# full_bridge_converter.net
KiCad netlist of a schematic drawn in Altium Designer
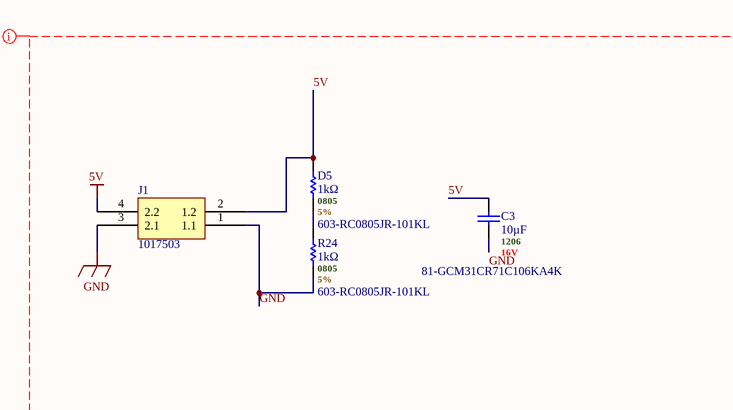
[diagram p0: full_bridge_converter.SchDoc, top left]
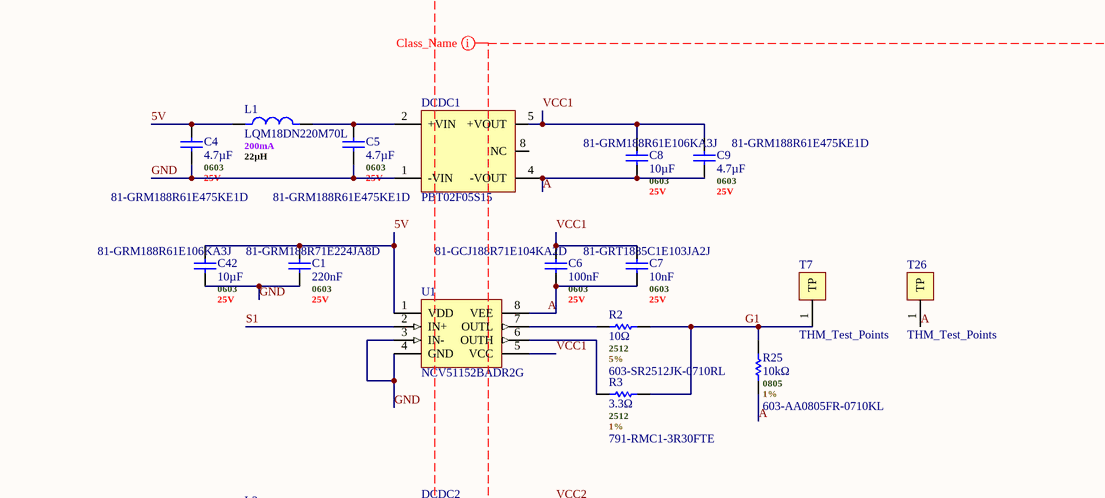
[diagram p1: full_bridge_converter.SchDoc, top right]
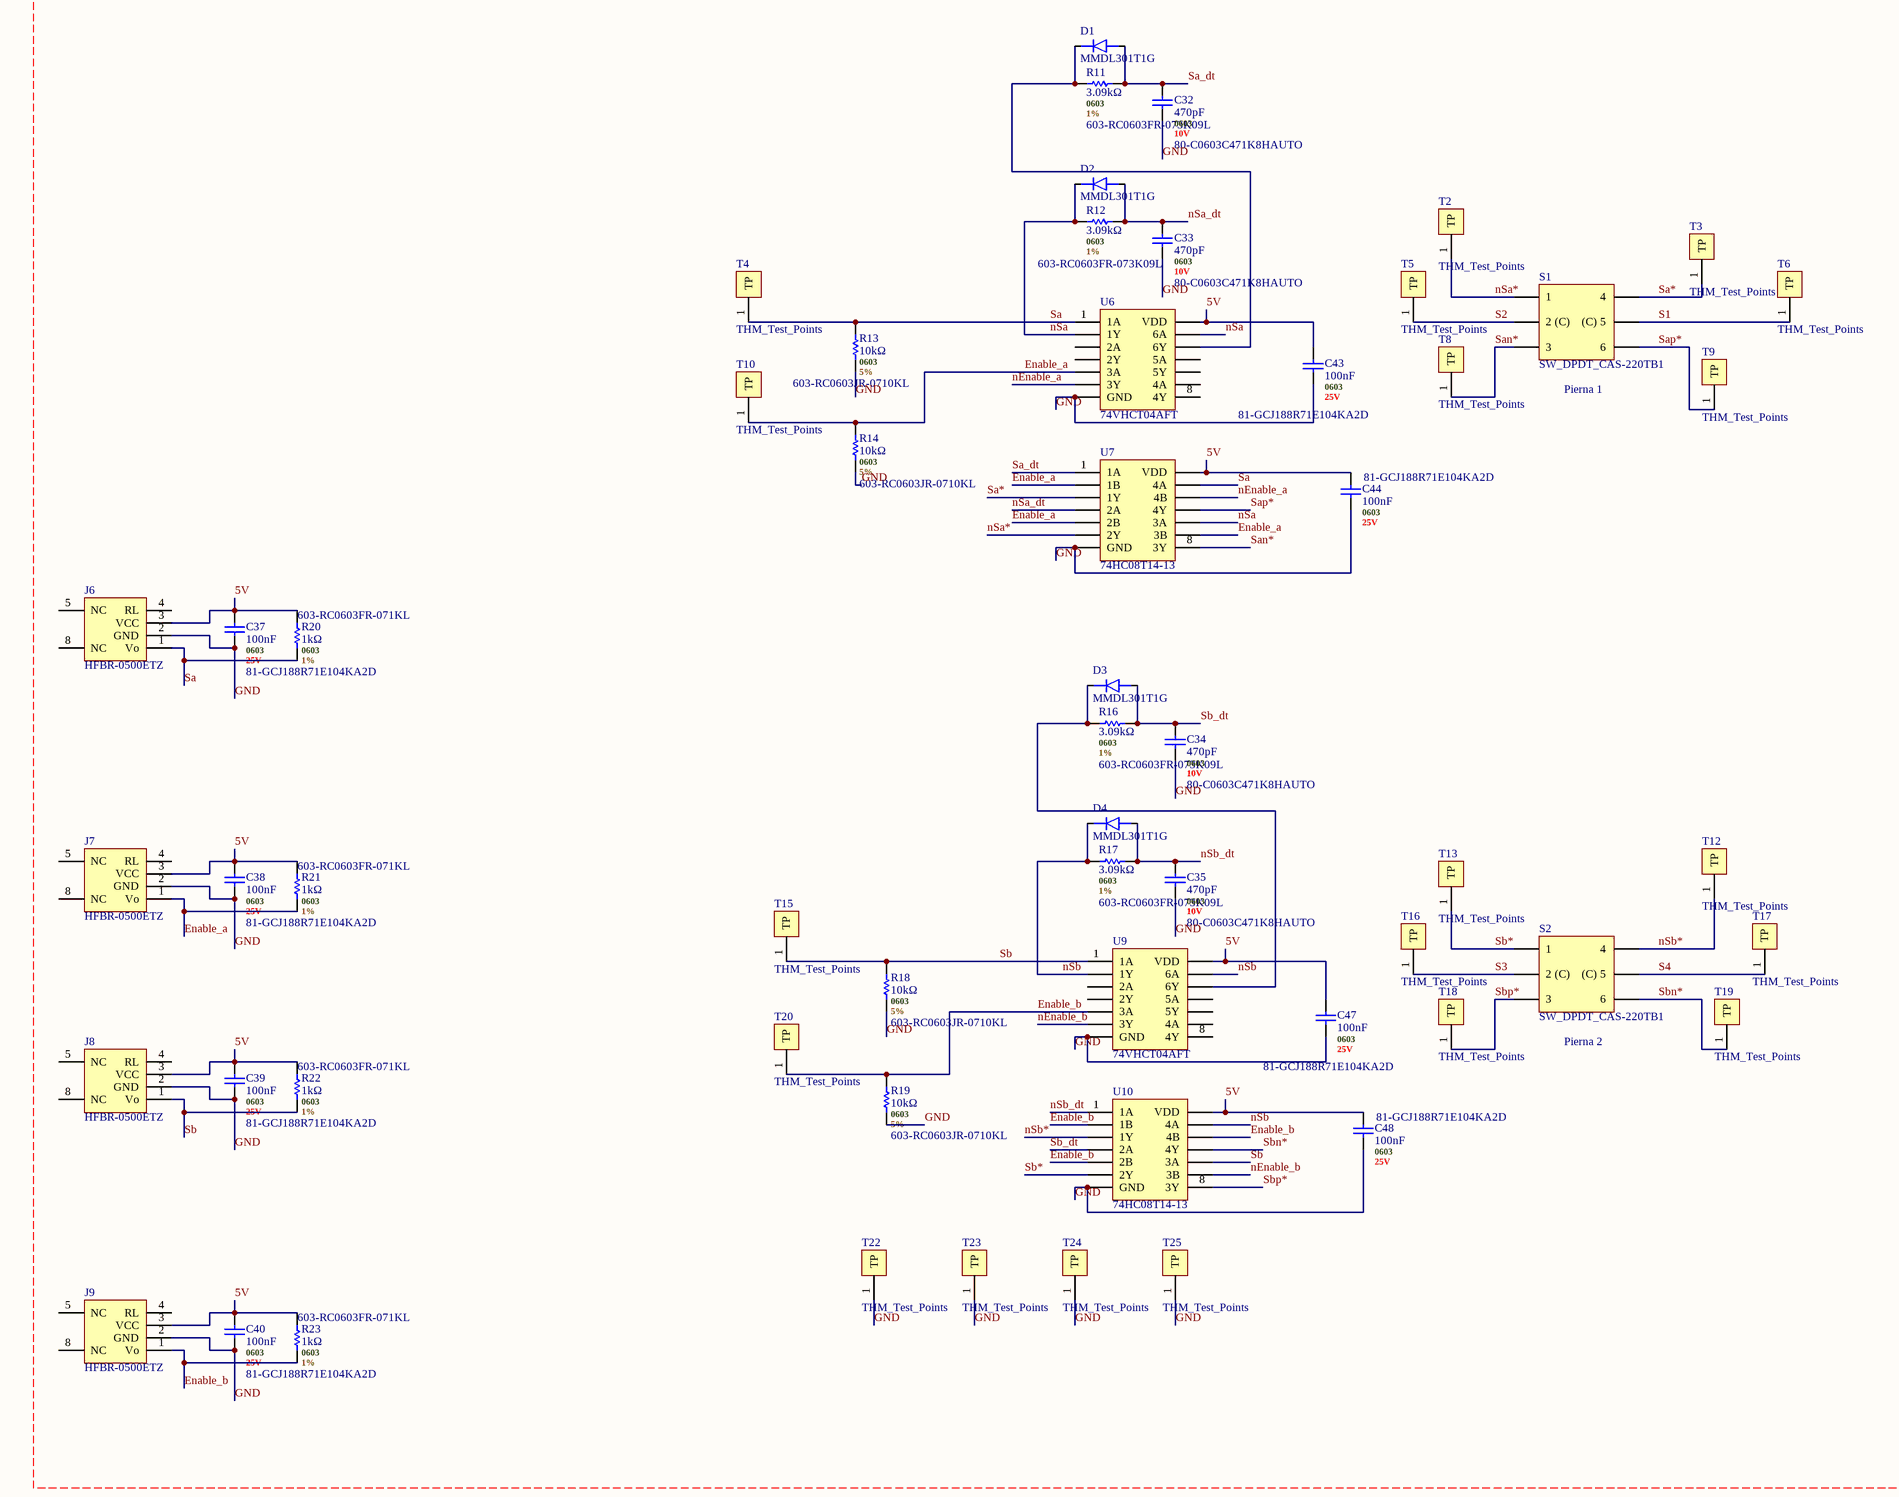
[diagram p2: full_bridge_converter.SchDoc, bottom left]
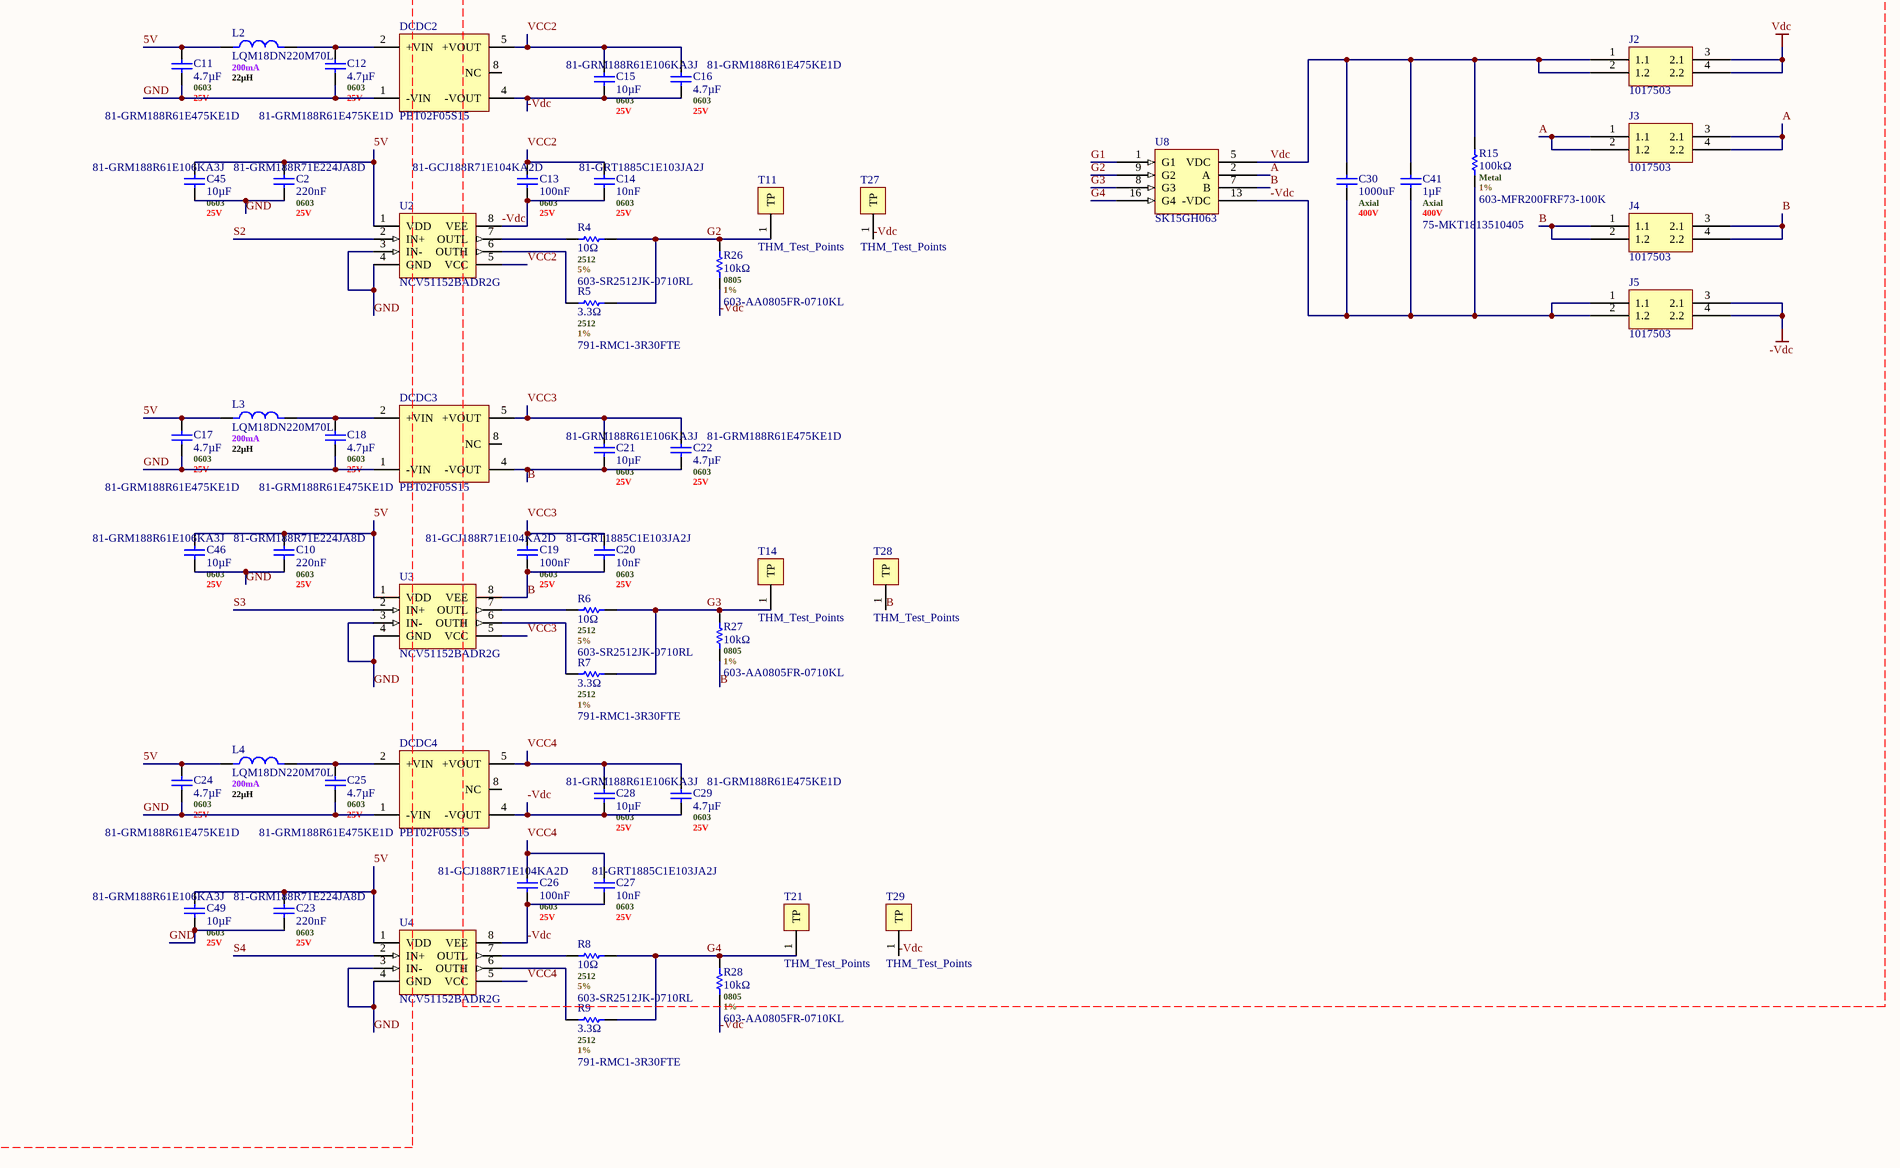
[diagram p3: full_bridge_converter.SchDoc, bottom right]

(export (version "E")
  (design (tool "Eeschema 10.0.6"))
  (components
    (comp (ref "C1")
      (value "220nF")
      (footprint "GRM188R71E224JA88D")
      (description "Ceramic Capacitor, Ceramic, 25V, 5% +Tol, 5% -Tol, X7R, 15% TC, 0.22uF, Surface Mount, 0603")
      (fields
        (field (name "MANUFACTURER") "Murata")
        (field (name "MANUFACTURER PART NUMBER") "GRM188R71E224JA88D")
        (field (name ".CASE/PACKAGE") "0603")
        (field (name ".VOLTAGE RATING (DC)") "25V")
        (field (name "SUPPLIER PART NUMBER 1") "81-GRM188R71E224JA8D")
      )
      (libsource (lib "CAP_GRM188R71E224JA88D") (part "CAP_GRM188R71E224JA88D"))
    )
    (comp (ref "C2")
      (value "220nF")
      (footprint "GRM188R71E224JA88D")
      (description "Ceramic Capacitor, Ceramic, 25V, 5% +Tol, 5% -Tol, X7R, 15% TC, 0.22uF, Surface Mount, 0603")
      (fields
        (field (name "MANUFACTURER") "Murata")
        (field (name "MANUFACTURER PART NUMBER") "GRM188R71E224JA88D")
        (field (name ".CASE/PACKAGE") "0603")
        (field (name ".VOLTAGE RATING (DC)") "25V")
        (field (name "SUPPLIER PART NUMBER 1") "81-GRM188R71E224JA8D")
      )
      (libsource (lib "CAP_GRM188R71E224JA88D") (part "CAP_GRM188R71E224JA88D"))
    )
    (comp (ref "C3")
      (value "10µF")
      (footprint "GCM31CR71C106KA64K")
      (description "16V 10uF X7R ±10% 1206 Multilayer Ceramic Capacitors MLCC - SMD/SMT ROHS")
      (fields
        (field (name "MANUFACTURER") "Murata")
        (field (name "MANUFACTURER PART NUMBER") "GCM31CR71C106KA64K")
        (field (name ".CASE/PACKAGE") "1206")
        (field (name ".VOLTAGE RATING (DC)") "16V")
        (field (name "SUPPLIER PART NUMBER 1") "81-GCM31CR71C106KA4K")
      )
      (libsource (lib "CAP_Murata_GCM31CR71C106KA64K") (part "GCM31CR71C106KA4K"))
    )
    (comp (ref "C4")
      (value "4.7µF")
      (footprint "GRM188R71E224JA88D")
      (description "0603 4.7 uF 25 V ±10 % Tolerance X5R SMT Multilayer Ceramic Capacitor")
      (fields
        (field (name "MANUFACTURER") "Murata")
        (field (name "MANUFACTURER PART NUMBER") "GRM188R61E475KE11D")
        (field (name ".CASE/PACKAGE") "0603")
        (field (name ".VOLTAGE RATING (DC)") "25V")
        (field (name "SUPPLIER PART NUMBER 1") "81-GRM188R61E475KE1D")
      )
      (libsource (lib "CAP_GRM188R61E475KE11D") (part "CAP_GRM188R61E475KE11D"))
    )
    (comp (ref "C5")
      (value "4.7µF")
      (footprint "GRM188R71E224JA88D")
      (description "0603 4.7 uF 25 V ±10 % Tolerance X5R SMT Multilayer Ceramic Capacitor")
      (fields
        (field (name "MANUFACTURER") "Murata")
        (field (name "MANUFACTURER PART NUMBER") "GRM188R61E475KE11D")
        (field (name ".CASE/PACKAGE") "0603")
        (field (name ".VOLTAGE RATING (DC)") "25V")
        (field (name "SUPPLIER PART NUMBER 1") "81-GRM188R61E475KE1D")
      )
      (libsource (lib "CAP_GRM188R61E475KE11D") (part "CAP_GRM188R61E475KE11D"))
    )
    (comp (ref "C6")
      (value "100nF")
      (footprint "GRM188R71E224JA88D")
      (description "Ceramic Capacitor, Ceramic, 25V, 10% +Tol, 10% -Tol, X7R, 15% TC, 0.1uF, Surface Mount, 0603")
      (fields
        (field (name "MANUFACTURER") "Murata")
        (field (name "MANUFACTURER PART NUMBER") "GCJ188R71E104KA12D")
        (field (name ".CASE/PACKAGE") "0603")
        (field (name ".VOLTAGE RATING (DC)") "25V")
        (field (name "SUPPLIER PART NUMBER 1") "81-GCJ188R71E104KA2D")
      )
      (libsource (lib "CAP_GCJ188R71E104KA12D") (part "CAP_GCJ188R71E104KA12D"))
    )
    (comp (ref "C7")
      (value "10nF")
      (footprint "GRM188R71E224JA88D")
      (description "Multi-Layer Ceramic Capacitor 0.01uF 25VDC C0G 5% 0603 Paper T/R")
      (fields
        (field (name "MANUFACTURER") "Murata")
        (field (name "MANUFACTURER PART NUMBER") "GRT1885C1E103JA02J")
        (field (name ".CASE/PACKAGE") "0603")
        (field (name ".VOLTAGE RATING (DC)") "25V")
        (field (name "SUPPLIER PART NUMBER 1") "81-GRT1885C1E103JA2J")
      )
      (libsource (lib "CAP_GRT1885C1E103JA02J") (part "GRT1885C1E103JA02J"))
    )
    (comp (ref "C8")
      (value "10µF")
      (footprint "GRM188R71E224JA88D")
      (description "Multilayer Ceramic Capacitor, 10 uF, 25 V, 10%, X5R, 0603 1608 Metric - T/R")
      (fields
        (field (name "MANUFACTURER") "Murata")
        (field (name "MANUFACTURER PART NUMBER") "GRM188R61E106KA73J")
        (field (name ".CASE/PACKAGE") "0603")
        (field (name ".VOLTAGE RATING (DC)") "25V")
        (field (name "SUPPLIER PART NUMBER 1") "81-GRM188R61E106KA3J")
      )
      (libsource (lib "CAP_GRM188R61E106KA73J") (part "CAP_GRM188R61E106KA73J"))
    )
    (comp (ref "C9")
      (value "4.7µF")
      (footprint "GRM188R71E224JA88D")
      (description "0603 4.7 uF 25 V ±10 % Tolerance X5R SMT Multilayer Ceramic Capacitor")
      (fields
        (field (name "MANUFACTURER") "Murata")
        (field (name "MANUFACTURER PART NUMBER") "GRM188R61E475KE11D")
        (field (name ".CASE/PACKAGE") "0603")
        (field (name ".VOLTAGE RATING (DC)") "25V")
        (field (name "SUPPLIER PART NUMBER 1") "81-GRM188R61E475KE1D")
      )
      (libsource (lib "CAP_GRM188R61E475KE11D") (part "CAP_GRM188R61E475KE11D"))
    )
    (comp (ref "C10")
      (value "220nF")
      (footprint "GRM188R71E224JA88D")
      (description "Ceramic Capacitor, Ceramic, 25V, 5% +Tol, 5% -Tol, X7R, 15% TC, 0.22uF, Surface Mount, 0603")
      (fields
        (field (name "MANUFACTURER") "Murata")
        (field (name "MANUFACTURER PART NUMBER") "GRM188R71E224JA88D")
        (field (name ".CASE/PACKAGE") "0603")
        (field (name ".VOLTAGE RATING (DC)") "25V")
        (field (name "SUPPLIER PART NUMBER 1") "81-GRM188R71E224JA8D")
      )
      (libsource (lib "CAP_GRM188R71E224JA88D") (part "CAP_GRM188R71E224JA88D"))
    )
    (comp (ref "C11")
      (value "4.7µF")
      (footprint "GRM188R71E224JA88D")
      (description "0603 4.7 uF 25 V ±10 % Tolerance X5R SMT Multilayer Ceramic Capacitor")
      (fields
        (field (name "MANUFACTURER") "Murata")
        (field (name "MANUFACTURER PART NUMBER") "GRM188R61E475KE11D")
        (field (name ".CASE/PACKAGE") "0603")
        (field (name ".VOLTAGE RATING (DC)") "25V")
        (field (name "SUPPLIER PART NUMBER 1") "81-GRM188R61E475KE1D")
      )
      (libsource (lib "CAP_GRM188R61E475KE11D") (part "CAP_GRM188R61E475KE11D"))
    )
    (comp (ref "C12")
      (value "4.7µF")
      (footprint "GRM188R71E224JA88D")
      (description "0603 4.7 uF 25 V ±10 % Tolerance X5R SMT Multilayer Ceramic Capacitor")
      (fields
        (field (name "MANUFACTURER") "Murata")
        (field (name "MANUFACTURER PART NUMBER") "GRM188R61E475KE11D")
        (field (name ".CASE/PACKAGE") "0603")
        (field (name ".VOLTAGE RATING (DC)") "25V")
        (field (name "SUPPLIER PART NUMBER 1") "81-GRM188R61E475KE1D")
      )
      (libsource (lib "CAP_GRM188R61E475KE11D") (part "CAP_GRM188R61E475KE11D"))
    )
    (comp (ref "C13")
      (value "100nF")
      (footprint "GRM188R71E224JA88D")
      (description "Ceramic Capacitor, Ceramic, 25V, 10% +Tol, 10% -Tol, X7R, 15% TC, 0.1uF, Surface Mount, 0603")
      (fields
        (field (name "MANUFACTURER") "Murata")
        (field (name "MANUFACTURER PART NUMBER") "GCJ188R71E104KA12D")
        (field (name ".CASE/PACKAGE") "0603")
        (field (name ".VOLTAGE RATING (DC)") "25V")
        (field (name "SUPPLIER PART NUMBER 1") "81-GCJ188R71E104KA2D")
      )
      (libsource (lib "CAP_GCJ188R71E104KA12D") (part "CAP_GCJ188R71E104KA12D"))
    )
    (comp (ref "C14")
      (value "10nF")
      (footprint "GRM188R71E224JA88D")
      (description "Multi-Layer Ceramic Capacitor 0.01uF 25VDC C0G 5% 0603 Paper T/R")
      (fields
        (field (name "MANUFACTURER") "Murata")
        (field (name "MANUFACTURER PART NUMBER") "GRT1885C1E103JA02J")
        (field (name ".CASE/PACKAGE") "0603")
        (field (name ".VOLTAGE RATING (DC)") "25V")
        (field (name "SUPPLIER PART NUMBER 1") "81-GRT1885C1E103JA2J")
      )
      (libsource (lib "CAP_GRT1885C1E103JA02J") (part "GRT1885C1E103JA02J"))
    )
    (comp (ref "C15")
      (value "10µF")
      (footprint "GRM188R71E224JA88D")
      (description "Multilayer Ceramic Capacitor, 10 uF, 25 V, 10%, X5R, 0603 1608 Metric - T/R")
      (fields
        (field (name "MANUFACTURER") "Murata")
        (field (name "MANUFACTURER PART NUMBER") "GRM188R61E106KA73J")
        (field (name ".CASE/PACKAGE") "0603")
        (field (name ".VOLTAGE RATING (DC)") "25V")
        (field (name "SUPPLIER PART NUMBER 1") "81-GRM188R61E106KA3J")
      )
      (libsource (lib "CAP_GRM188R61E106KA73J") (part "CAP_GRM188R61E106KA73J"))
    )
    (comp (ref "C16")
      (value "4.7µF")
      (footprint "GRM188R71E224JA88D")
      (description "0603 4.7 uF 25 V ±10 % Tolerance X5R SMT Multilayer Ceramic Capacitor")
      (fields
        (field (name "MANUFACTURER") "Murata")
        (field (name "MANUFACTURER PART NUMBER") "GRM188R61E475KE11D")
        (field (name ".CASE/PACKAGE") "0603")
        (field (name ".VOLTAGE RATING (DC)") "25V")
        (field (name "SUPPLIER PART NUMBER 1") "81-GRM188R61E475KE1D")
      )
      (libsource (lib "CAP_GRM188R61E475KE11D") (part "CAP_GRM188R61E475KE11D"))
    )
    (comp (ref "C17")
      (value "4.7µF")
      (footprint "GRM188R71E224JA88D")
      (description "0603 4.7 uF 25 V ±10 % Tolerance X5R SMT Multilayer Ceramic Capacitor")
      (fields
        (field (name "MANUFACTURER") "Murata")
        (field (name "MANUFACTURER PART NUMBER") "GRM188R61E475KE11D")
        (field (name ".CASE/PACKAGE") "0603")
        (field (name ".VOLTAGE RATING (DC)") "25V")
        (field (name "SUPPLIER PART NUMBER 1") "81-GRM188R61E475KE1D")
      )
      (libsource (lib "CAP_GRM188R61E475KE11D") (part "CAP_GRM188R61E475KE11D"))
    )
    (comp (ref "C18")
      (value "4.7µF")
      (footprint "GRM188R71E224JA88D")
      (description "0603 4.7 uF 25 V ±10 % Tolerance X5R SMT Multilayer Ceramic Capacitor")
      (fields
        (field (name "MANUFACTURER") "Murata")
        (field (name "MANUFACTURER PART NUMBER") "GRM188R61E475KE11D")
        (field (name ".CASE/PACKAGE") "0603")
        (field (name ".VOLTAGE RATING (DC)") "25V")
        (field (name "SUPPLIER PART NUMBER 1") "81-GRM188R61E475KE1D")
      )
      (libsource (lib "CAP_GRM188R61E475KE11D") (part "CAP_GRM188R61E475KE11D"))
    )
    (comp (ref "C19")
      (value "100nF")
      (footprint "GRM188R71E224JA88D")
      (description "Ceramic Capacitor, Ceramic, 25V, 10% +Tol, 10% -Tol, X7R, 15% TC, 0.1uF, Surface Mount, 0603")
      (fields
        (field (name "MANUFACTURER") "Murata")
        (field (name "MANUFACTURER PART NUMBER") "GCJ188R71E104KA12D")
        (field (name ".CASE/PACKAGE") "0603")
        (field (name ".VOLTAGE RATING (DC)") "25V")
        (field (name "SUPPLIER PART NUMBER 1") "81-GCJ188R71E104KA2D")
      )
      (libsource (lib "CAP_GCJ188R71E104KA12D") (part "CAP_GCJ188R71E104KA12D"))
    )
    (comp (ref "C20")
      (value "10nF")
      (footprint "GRM188R71E224JA88D")
      (description "Multi-Layer Ceramic Capacitor 0.01uF 25VDC C0G 5% 0603 Paper T/R")
      (fields
        (field (name "MANUFACTURER") "Murata")
        (field (name "MANUFACTURER PART NUMBER") "GRT1885C1E103JA02J")
        (field (name ".CASE/PACKAGE") "0603")
        (field (name ".VOLTAGE RATING (DC)") "25V")
        (field (name "SUPPLIER PART NUMBER 1") "81-GRT1885C1E103JA2J")
      )
      (libsource (lib "CAP_GRT1885C1E103JA02J") (part "GRT1885C1E103JA02J"))
    )
    (comp (ref "C21")
      (value "10µF")
      (footprint "GRM188R71E224JA88D")
      (description "Multilayer Ceramic Capacitor, 10 uF, 25 V, 10%, X5R, 0603 1608 Metric - T/R")
      (fields
        (field (name "MANUFACTURER") "Murata")
        (field (name "MANUFACTURER PART NUMBER") "GRM188R61E106KA73J")
        (field (name ".CASE/PACKAGE") "0603")
        (field (name ".VOLTAGE RATING (DC)") "25V")
        (field (name "SUPPLIER PART NUMBER 1") "81-GRM188R61E106KA3J")
      )
      (libsource (lib "CAP_GRM188R61E106KA73J") (part "CAP_GRM188R61E106KA73J"))
    )
    (comp (ref "C22")
      (value "4.7µF")
      (footprint "GRM188R71E224JA88D")
      (description "0603 4.7 uF 25 V ±10 % Tolerance X5R SMT Multilayer Ceramic Capacitor")
      (fields
        (field (name "MANUFACTURER") "Murata")
        (field (name "MANUFACTURER PART NUMBER") "GRM188R61E475KE11D")
        (field (name ".CASE/PACKAGE") "0603")
        (field (name ".VOLTAGE RATING (DC)") "25V")
        (field (name "SUPPLIER PART NUMBER 1") "81-GRM188R61E475KE1D")
      )
      (libsource (lib "CAP_GRM188R61E475KE11D") (part "CAP_GRM188R61E475KE11D"))
    )
    (comp (ref "C23")
      (value "220nF")
      (footprint "GRM188R71E224JA88D")
      (description "Ceramic Capacitor, Ceramic, 25V, 5% +Tol, 5% -Tol, X7R, 15% TC, 0.22uF, Surface Mount, 0603")
      (fields
        (field (name "MANUFACTURER") "Murata")
        (field (name "MANUFACTURER PART NUMBER") "GRM188R71E224JA88D")
        (field (name ".CASE/PACKAGE") "0603")
        (field (name ".VOLTAGE RATING (DC)") "25V")
        (field (name "SUPPLIER PART NUMBER 1") "81-GRM188R71E224JA8D")
      )
      (libsource (lib "CAP_GRM188R71E224JA88D") (part "CAP_GRM188R71E224JA88D"))
    )
    (comp (ref "C24")
      (value "4.7µF")
      (footprint "GRM188R71E224JA88D")
      (description "0603 4.7 uF 25 V ±10 % Tolerance X5R SMT Multilayer Ceramic Capacitor")
      (fields
        (field (name "MANUFACTURER") "Murata")
        (field (name "MANUFACTURER PART NUMBER") "GRM188R61E475KE11D")
        (field (name ".CASE/PACKAGE") "0603")
        (field (name ".VOLTAGE RATING (DC)") "25V")
        (field (name "SUPPLIER PART NUMBER 1") "81-GRM188R61E475KE1D")
      )
      (libsource (lib "CAP_GRM188R61E475KE11D") (part "CAP_GRM188R61E475KE11D"))
    )
    (comp (ref "C25")
      (value "4.7µF")
      (footprint "GRM188R71E224JA88D")
      (description "0603 4.7 uF 25 V ±10 % Tolerance X5R SMT Multilayer Ceramic Capacitor")
      (fields
        (field (name "MANUFACTURER") "Murata")
        (field (name "MANUFACTURER PART NUMBER") "GRM188R61E475KE11D")
        (field (name ".CASE/PACKAGE") "0603")
        (field (name ".VOLTAGE RATING (DC)") "25V")
        (field (name "SUPPLIER PART NUMBER 1") "81-GRM188R61E475KE1D")
      )
      (libsource (lib "CAP_GRM188R61E475KE11D") (part "CAP_GRM188R61E475KE11D"))
    )
    (comp (ref "C26")
      (value "100nF")
      (footprint "GRM188R71E224JA88D")
      (description "Ceramic Capacitor, Ceramic, 25V, 10% +Tol, 10% -Tol, X7R, 15% TC, 0.1uF, Surface Mount, 0603")
      (fields
        (field (name "MANUFACTURER") "Murata")
        (field (name "MANUFACTURER PART NUMBER") "GCJ188R71E104KA12D")
        (field (name ".CASE/PACKAGE") "0603")
        (field (name ".VOLTAGE RATING (DC)") "25V")
        (field (name "SUPPLIER PART NUMBER 1") "81-GCJ188R71E104KA2D")
      )
      (libsource (lib "CAP_GCJ188R71E104KA12D") (part "CAP_GCJ188R71E104KA12D"))
    )
    (comp (ref "C27")
      (value "10nF")
      (footprint "GRM188R71E224JA88D")
      (description "Multi-Layer Ceramic Capacitor 0.01uF 25VDC C0G 5% 0603 Paper T/R")
      (fields
        (field (name "MANUFACTURER") "Murata")
        (field (name "MANUFACTURER PART NUMBER") "GRT1885C1E103JA02J")
        (field (name ".CASE/PACKAGE") "0603")
        (field (name ".VOLTAGE RATING (DC)") "25V")
        (field (name "SUPPLIER PART NUMBER 1") "81-GRT1885C1E103JA2J")
      )
      (libsource (lib "CAP_GRT1885C1E103JA02J") (part "GRT1885C1E103JA02J"))
    )
    (comp (ref "C28")
      (value "10µF")
      (footprint "GRM188R71E224JA88D")
      (description "Multilayer Ceramic Capacitor, 10 uF, 25 V, 10%, X5R, 0603 1608 Metric - T/R")
      (fields
        (field (name "MANUFACTURER") "Murata")
        (field (name "MANUFACTURER PART NUMBER") "GRM188R61E106KA73J")
        (field (name ".CASE/PACKAGE") "0603")
        (field (name ".VOLTAGE RATING (DC)") "25V")
        (field (name "SUPPLIER PART NUMBER 1") "81-GRM188R61E106KA3J")
      )
      (libsource (lib "CAP_GRM188R61E106KA73J") (part "CAP_GRM188R61E106KA73J"))
    )
    (comp (ref "C29")
      (value "4.7µF")
      (footprint "GRM188R71E224JA88D")
      (description "0603 4.7 uF 25 V ±10 % Tolerance X5R SMT Multilayer Ceramic Capacitor")
      (fields
        (field (name "MANUFACTURER") "Murata")
        (field (name "MANUFACTURER PART NUMBER") "GRM188R61E475KE11D")
        (field (name ".CASE/PACKAGE") "0603")
        (field (name ".VOLTAGE RATING (DC)") "25V")
        (field (name "SUPPLIER PART NUMBER 1") "81-GRM188R61E475KE1D")
      )
      (libsource (lib "CAP_GRM188R61E475KE11D") (part "CAP_GRM188R61E475KE11D"))
    )
    (comp (ref "C30")
      (value "1000uF")
      (footprint "Pcb_Components:1316N")
      (fields
        (field (name "VOLTAGE") "400V")
        (field (name ".CASE/PACKAGE") "Axial")
        (field (name ".VOLTAGE RATING (DC)") "400V")
      )
      (libsource (lib "Sch_components") (part "Pana_400_1000"))
    )
    (comp (ref "C32")
      (value "470pF")
      (footprint "C0603 - MURATA")
      (description "Cap, 470Pf, 10V, Mlcc, 0603 Rohs Compliant: Yes ¦Kemet C0603C471K8HACAUTO")
      (fields
        (field (name "MANUFACTURER") "KEMET")
        (field (name "MANUFACTURER PART NUMBER") "C0603C471K8HACAUTO")
        (field (name ".CASE/PACKAGE") "0603")
        (field (name ".VOLTAGE RATING (DC)") "10V")
        (field (name "SUPPLIER PART NUMBER 1") "80-C0603C471K8HAUTO")
      )
      (libsource (lib "CAP_C0603C471K8HACAUTO") (part "CAP_Kemet_C0603C471K8HACAUTO"))
    )
    (comp (ref "C33")
      (value "470pF")
      (footprint "C0603 - MURATA")
      (description "Cap, 470Pf, 10V, Mlcc, 0603 Rohs Compliant: Yes ¦Kemet C0603C471K8HACAUTO")
      (fields
        (field (name "MANUFACTURER") "KEMET")
        (field (name "MANUFACTURER PART NUMBER") "C0603C471K8HACAUTO")
        (field (name ".CASE/PACKAGE") "0603")
        (field (name ".VOLTAGE RATING (DC)") "10V")
        (field (name "SUPPLIER PART NUMBER 1") "80-C0603C471K8HAUTO")
      )
      (libsource (lib "CAP_C0603C471K8HACAUTO") (part "CAP_Kemet_C0603C471K8HACAUTO"))
    )
    (comp (ref "C34")
      (value "470pF")
      (footprint "C0603 - MURATA")
      (description "Cap, 470Pf, 10V, Mlcc, 0603 Rohs Compliant: Yes ¦Kemet C0603C471K8HACAUTO")
      (fields
        (field (name "MANUFACTURER") "KEMET")
        (field (name "MANUFACTURER PART NUMBER") "C0603C471K8HACAUTO")
        (field (name ".CASE/PACKAGE") "0603")
        (field (name ".VOLTAGE RATING (DC)") "10V")
        (field (name "SUPPLIER PART NUMBER 1") "80-C0603C471K8HAUTO")
      )
      (libsource (lib "CAP_C0603C471K8HACAUTO") (part "CAP_Kemet_C0603C471K8HACAUTO"))
    )
    (comp (ref "C35")
      (value "470pF")
      (footprint "C0603 - MURATA")
      (description "Cap, 470Pf, 10V, Mlcc, 0603 Rohs Compliant: Yes ¦Kemet C0603C471K8HACAUTO")
      (fields
        (field (name "MANUFACTURER") "KEMET")
        (field (name "MANUFACTURER PART NUMBER") "C0603C471K8HACAUTO")
        (field (name ".CASE/PACKAGE") "0603")
        (field (name ".VOLTAGE RATING (DC)") "10V")
        (field (name "SUPPLIER PART NUMBER 1") "80-C0603C471K8HAUTO")
      )
      (libsource (lib "CAP_C0603C471K8HACAUTO") (part "CAP_Kemet_C0603C471K8HACAUTO"))
    )
    (comp (ref "C37")
      (value "100nF")
      (footprint "GRM188R71E224JA88D")
      (description "Ceramic Capacitor, Ceramic, 25V, 10% +Tol, 10% -Tol, X7R, 15% TC, 0.1uF, Surface Mount, 0603")
      (fields
        (field (name "MANUFACTURER") "Murata")
        (field (name "MANUFACTURER PART NUMBER") "GCJ188R71E104KA12D")
        (field (name ".CASE/PACKAGE") "0603")
        (field (name ".VOLTAGE RATING (DC)") "25V")
        (field (name "SUPPLIER PART NUMBER 1") "81-GCJ188R71E104KA2D")
      )
      (libsource (lib "CAP_GCJ188R71E104KA12D") (part "CAP_GCJ188R71E104KA12D"))
    )
    (comp (ref "C38")
      (value "100nF")
      (footprint "GRM188R71E224JA88D")
      (description "Ceramic Capacitor, Ceramic, 25V, 10% +Tol, 10% -Tol, X7R, 15% TC, 0.1uF, Surface Mount, 0603")
      (fields
        (field (name "MANUFACTURER") "Murata")
        (field (name "MANUFACTURER PART NUMBER") "GCJ188R71E104KA12D")
        (field (name ".CASE/PACKAGE") "0603")
        (field (name ".VOLTAGE RATING (DC)") "25V")
        (field (name "SUPPLIER PART NUMBER 1") "81-GCJ188R71E104KA2D")
      )
      (libsource (lib "CAP_GCJ188R71E104KA12D") (part "CAP_GCJ188R71E104KA12D"))
    )
    (comp (ref "C39")
      (value "100nF")
      (footprint "GRM188R71E224JA88D")
      (description "Ceramic Capacitor, Ceramic, 25V, 10% +Tol, 10% -Tol, X7R, 15% TC, 0.1uF, Surface Mount, 0603")
      (fields
        (field (name "MANUFACTURER") "Murata")
        (field (name "MANUFACTURER PART NUMBER") "GCJ188R71E104KA12D")
        (field (name ".CASE/PACKAGE") "0603")
        (field (name ".VOLTAGE RATING (DC)") "25V")
        (field (name "SUPPLIER PART NUMBER 1") "81-GCJ188R71E104KA2D")
      )
      (libsource (lib "CAP_GCJ188R71E104KA12D") (part "CAP_GCJ188R71E104KA12D"))
    )
    (comp (ref "C40")
      (value "100nF")
      (footprint "GRM188R71E224JA88D")
      (description "Ceramic Capacitor, Ceramic, 25V, 10% +Tol, 10% -Tol, X7R, 15% TC, 0.1uF, Surface Mount, 0603")
      (fields
        (field (name "MANUFACTURER") "Murata")
        (field (name "MANUFACTURER PART NUMBER") "GCJ188R71E104KA12D")
        (field (name ".CASE/PACKAGE") "0603")
        (field (name ".VOLTAGE RATING (DC)") "25V")
        (field (name "SUPPLIER PART NUMBER 1") "81-GCJ188R71E104KA2D")
      )
      (libsource (lib "CAP_GCJ188R71E104KA12D") (part "CAP_GCJ188R71E104KA12D"))
    )
    (comp (ref "C41")
      (value "1µF")
      (footprint "MKT1813510405")
      (description "Film Capacitor, Polyester, 400V, 10% +Tol, 10% -Tol, 1uF, Through Hole Mount")
      (fields
        (field (name "MANUFACTURER") "Vishay")
        (field (name "MANUFACTURER PART NUMBER") "MKT1813510405")
        (field (name ".CASE/PACKAGE") "Axial")
        (field (name ".VOLTAGE RATING (DC)") "400V")
        (field (name "SUPPLIER PART NUMBER 1") "75-MKT1813510405")
      )
      (libsource (lib "CAP_Vishay_MKT1813510405") (part "MKT1813510405"))
    )
    (comp (ref "C42")
      (value "10µF")
      (footprint "GRM188R71E224JA88D")
      (description "Multilayer Ceramic Capacitor, 10 uF, 25 V, 10%, X5R, 0603 1608 Metric - T/R")
      (fields
        (field (name "MANUFACTURER") "Murata")
        (field (name "MANUFACTURER PART NUMBER") "GRM188R61E106KA73J")
        (field (name ".CASE/PACKAGE") "0603")
        (field (name ".VOLTAGE RATING (DC)") "25V")
        (field (name "SUPPLIER PART NUMBER 1") "81-GRM188R61E106KA3J")
      )
      (libsource (lib "CAP_GRM188R61E106KA73J") (part "CAP_GRM188R61E106KA73J"))
    )
    (comp (ref "C43")
      (value "100nF")
      (footprint "GRM188R71E224JA88D")
      (description "Ceramic Capacitor, Ceramic, 25V, 10% +Tol, 10% -Tol, X7R, 15% TC, 0.1uF, Surface Mount, 0603")
      (fields
        (field (name "MANUFACTURER") "Murata")
        (field (name "MANUFACTURER PART NUMBER") "GCJ188R71E104KA12D")
        (field (name ".CASE/PACKAGE") "0603")
        (field (name ".VOLTAGE RATING (DC)") "25V")
        (field (name "SUPPLIER PART NUMBER 1") "81-GCJ188R71E104KA2D")
      )
      (libsource (lib "CAP_GCJ188R71E104KA12D") (part "CAP_GCJ188R71E104KA12D"))
    )
    (comp (ref "C44")
      (value "100nF")
      (footprint "GRM188R71E224JA88D")
      (description "Ceramic Capacitor, Ceramic, 25V, 10% +Tol, 10% -Tol, X7R, 15% TC, 0.1uF, Surface Mount, 0603")
      (fields
        (field (name "MANUFACTURER") "Murata")
        (field (name "MANUFACTURER PART NUMBER") "GCJ188R71E104KA12D")
        (field (name ".CASE/PACKAGE") "0603")
        (field (name ".VOLTAGE RATING (DC)") "25V")
        (field (name "SUPPLIER PART NUMBER 1") "81-GCJ188R71E104KA2D")
      )
      (libsource (lib "CAP_GCJ188R71E104KA12D") (part "CAP_GCJ188R71E104KA12D"))
    )
    (comp (ref "C45")
      (value "10µF")
      (footprint "GRM188R71E224JA88D")
      (description "Multilayer Ceramic Capacitor, 10 uF, 25 V, 10%, X5R, 0603 1608 Metric - T/R")
      (fields
        (field (name "MANUFACTURER") "Murata")
        (field (name "MANUFACTURER PART NUMBER") "GRM188R61E106KA73J")
        (field (name ".CASE/PACKAGE") "0603")
        (field (name ".VOLTAGE RATING (DC)") "25V")
        (field (name "SUPPLIER PART NUMBER 1") "81-GRM188R61E106KA3J")
      )
      (libsource (lib "CAP_GRM188R61E106KA73J") (part "CAP_GRM188R61E106KA73J"))
    )
    (comp (ref "C46")
      (value "10µF")
      (footprint "GRM188R71E224JA88D")
      (description "Multilayer Ceramic Capacitor, 10 uF, 25 V, 10%, X5R, 0603 1608 Metric - T/R")
      (fields
        (field (name "MANUFACTURER") "Murata")
        (field (name "MANUFACTURER PART NUMBER") "GRM188R61E106KA73J")
        (field (name ".CASE/PACKAGE") "0603")
        (field (name ".VOLTAGE RATING (DC)") "25V")
        (field (name "SUPPLIER PART NUMBER 1") "81-GRM188R61E106KA3J")
      )
      (libsource (lib "CAP_GRM188R61E106KA73J") (part "CAP_GRM188R61E106KA73J"))
    )
    (comp (ref "C47")
      (value "100nF")
      (footprint "GRM188R71E224JA88D")
      (description "Ceramic Capacitor, Ceramic, 25V, 10% +Tol, 10% -Tol, X7R, 15% TC, 0.1uF, Surface Mount, 0603")
      (fields
        (field (name "MANUFACTURER") "Murata")
        (field (name "MANUFACTURER PART NUMBER") "GCJ188R71E104KA12D")
        (field (name ".CASE/PACKAGE") "0603")
        (field (name ".VOLTAGE RATING (DC)") "25V")
        (field (name "SUPPLIER PART NUMBER 1") "81-GCJ188R71E104KA2D")
      )
      (libsource (lib "CAP_GCJ188R71E104KA12D") (part "CAP_GCJ188R71E104KA12D"))
    )
    (comp (ref "C48")
      (value "100nF")
      (footprint "GRM188R71E224JA88D")
      (description "Ceramic Capacitor, Ceramic, 25V, 10% +Tol, 10% -Tol, X7R, 15% TC, 0.1uF, Surface Mount, 0603")
      (fields
        (field (name "MANUFACTURER") "Murata")
        (field (name "MANUFACTURER PART NUMBER") "GCJ188R71E104KA12D")
        (field (name ".CASE/PACKAGE") "0603")
        (field (name ".VOLTAGE RATING (DC)") "25V")
        (field (name "SUPPLIER PART NUMBER 1") "81-GCJ188R71E104KA2D")
      )
      (libsource (lib "CAP_GCJ188R71E104KA12D") (part "CAP_GCJ188R71E104KA12D"))
    )
    (comp (ref "C49")
      (value "10µF")
      (footprint "GRM188R71E224JA88D")
      (description "Multilayer Ceramic Capacitor, 10 uF, 25 V, 10%, X5R, 0603 1608 Metric - T/R")
      (fields
        (field (name "MANUFACTURER") "Murata")
        (field (name "MANUFACTURER PART NUMBER") "GRM188R61E106KA73J")
        (field (name ".CASE/PACKAGE") "0603")
        (field (name ".VOLTAGE RATING (DC)") "25V")
        (field (name "SUPPLIER PART NUMBER 1") "81-GRM188R61E106KA3J")
      )
      (libsource (lib "CAP_GRM188R61E106KA73J") (part "CAP_GRM188R61E106KA73J"))
    )
    (comp (ref "D1")
      (value "MMDL301T1G")
      (footprint "DIOM2713X12N")
      (libsource (lib "Sch_components") (part "MMDL301T1G"))
    )
    (comp (ref "D2")
      (value "MMDL301T1G")
      (footprint "DIOM2713X12N")
      (libsource (lib "Sch_components") (part "MMDL301T1G"))
    )
    (comp (ref "D3")
      (value "MMDL301T1G")
      (footprint "DIOM2713X12N")
      (libsource (lib "Sch_components") (part "MMDL301T1G"))
    )
    (comp (ref "D4")
      (value "MMDL301T1G")
      (footprint "DIOM2713X12N")
      (libsource (lib "Sch_components") (part "MMDL301T1G"))
    )
    (comp (ref "D5")
      (value "1kΩ")
      (footprint "RC0805JR-101KL")
      (description "Res Thick Film 0805 1K Ohm 5% 0.125W(1/8W) ±100ppm/C Pad SMD T/R")
      (fields
        (field (name "MANUFACTURER") "Yageo Group")
        (field (name "MANUFACTURER PART NUMBER") "RC0805JR-101KL")
        (field (name ".CASE/PACKAGE") "0805")
        (field (name ".TOLERANCE") "5%")
        (field (name "SUPPLIER PART NUMBER 1") "603-RC0805JR-101KL")
      )
      (libsource (lib "RESISTOR_Yageo_RC0805JR-101KL") (part "RC0805JR-101KL"))
    )
    (comp (ref "DCDC1")
      (value "PBT02F05S15")
      (footprint "PBT02F05S15")
      (libsource (lib "Sch_components") (part "PBT02F05S15"))
    )
    (comp (ref "DCDC2")
      (value "PBT02F05S15")
      (footprint "PBT02F05S15")
      (libsource (lib "Sch_components") (part "PBT02F05S15"))
    )
    (comp (ref "DCDC3")
      (value "PBT02F05S15")
      (footprint "PBT02F05S15")
      (libsource (lib "Sch_components") (part "PBT02F05S15"))
    )
    (comp (ref "DCDC4")
      (value "PBT02F05S15")
      (footprint "PBT02F05S15")
      (libsource (lib "Sch_components") (part "PBT02F05S15"))
    )
    (comp (ref "J1") (value "1017503") (footprint "CONN_1017491") (libsource (lib "") (part "1017503_1")))
    (comp (ref "J2")
      (value "1017503")
      (footprint "CONN_1017491")
      (libsource (lib "Phoenix_1017503") (part "1017503"))
    )
    (comp (ref "J3")
      (value "1017503")
      (footprint "CONN_1017491")
      (libsource (lib "Phoenix_1017503") (part "1017503"))
    )
    (comp (ref "J4")
      (value "1017503")
      (footprint "CONN_1017491")
      (libsource (lib "Phoenix_1017503") (part "1017503"))
    )
    (comp (ref "J5")
      (value "1017503")
      (footprint "CONN_1017491")
      (libsource (lib "Phoenix_1017503") (part "1017503"))
    )
    (comp (ref "J6")
      (value "HFBR-0500ETZ")
      (footprint "HFBR-0500ETZ")
      (description "Receptor Connector Optical Fiber")
      (libsource (lib "FibraOpt_Broadcom_HFBR") (part "HFBR-0500ETZ"))
    )
    (comp (ref "J7")
      (value "HFBR-0500ETZ")
      (footprint "HFBR-0500ETZ")
      (description "Receptor Connector Optical Fiber")
      (libsource (lib "FibraOpt_Broadcom_HFBR") (part "HFBR-0500ETZ"))
    )
    (comp (ref "J8")
      (value "HFBR-0500ETZ")
      (footprint "HFBR-0500ETZ")
      (description "Receptor Connector Optical Fiber")
      (libsource (lib "FibraOpt_Broadcom_HFBR") (part "HFBR-0500ETZ"))
    )
    (comp (ref "J9")
      (value "HFBR-0500ETZ")
      (footprint "HFBR-0500ETZ")
      (description "Receptor Connector Optical Fiber")
      (libsource (lib "FibraOpt_Broadcom_HFBR") (part "HFBR-0500ETZ"))
    )
    (comp (ref "L1")
      (value "LQM18DN220M70L")
      (footprint "LQM18DN220M70L")
      (description "Inductor Power Shielded Multi-Layer 22uH 20% 1MHz Ferrite 0.2A 3.12Ohm DCR 0603 T/R")
      (fields
        (field (name "MANUFACTURER") "Murata")
        (field (name "TOLERANCE") "20%")
        (field (name ".RMS CURRENT (IRMS)") "200mA")
        (field (name ".VALUE") "22µH")
      )
      (libsource (lib "INDUC_Murata_LQM18DN220M70L") (part "LQM18DN220M70L"))
    )
    (comp (ref "L2")
      (value "LQM18DN220M70L")
      (footprint "LQM18DN220M70L")
      (description "Inductor Power Shielded Multi-Layer 22uH 20% 1MHz Ferrite 0.2A 3.12Ohm DCR 0603 T/R")
      (fields
        (field (name "MANUFACTURER") "Murata")
        (field (name "TOLERANCE") "20%")
        (field (name ".RMS CURRENT (IRMS)") "200mA")
        (field (name ".VALUE") "22µH")
      )
      (libsource (lib "INDUC_Murata_LQM18DN220M70L") (part "LQM18DN220M70L"))
    )
    (comp (ref "L3")
      (value "LQM18DN220M70L")
      (footprint "LQM18DN220M70L")
      (description "Inductor Power Shielded Multi-Layer 22uH 20% 1MHz Ferrite 0.2A 3.12Ohm DCR 0603 T/R")
      (fields
        (field (name "MANUFACTURER") "Murata")
        (field (name "TOLERANCE") "20%")
        (field (name ".RMS CURRENT (IRMS)") "200mA")
        (field (name ".VALUE") "22µH")
      )
      (libsource (lib "INDUC_Murata_LQM18DN220M70L") (part "LQM18DN220M70L"))
    )
    (comp (ref "L4")
      (value "LQM18DN220M70L")
      (footprint "LQM18DN220M70L")
      (description "Inductor Power Shielded Multi-Layer 22uH 20% 1MHz Ferrite 0.2A 3.12Ohm DCR 0603 T/R")
      (fields
        (field (name "MANUFACTURER") "Murata")
        (field (name "TOLERANCE") "20%")
        (field (name ".RMS CURRENT (IRMS)") "200mA")
        (field (name ".VALUE") "22µH")
      )
      (libsource (lib "INDUC_Murata_LQM18DN220M70L") (part "LQM18DN220M70L"))
    )
    (comp (ref "R2")
      (value "10Ω")
      (footprint "SR2512JK-0710RL")
      (fields
        (field (name "MANUFACTURER") "Yageo Group")
        (field (name "MANUFACTURER PART NUMBER") "SR2512JK-0710RL")
        (field (name "TOLERANCE") "5%")
        (field (name ".CASE/PACKAGE") "2512")
        (field (name ".TOLERANCE") "5%")
        (field (name "SUPPLIER PART NUMBER 1") "603-SR2512JK-0710RL")
      )
      (libsource (lib "RESISTOR_Yageo_SR2512JK-0710RL") (part "SR2512JK-0710RL"))
    )
    (comp (ref "R3")
      (value "3.3Ω")
      (footprint "RMC1-3R30FTE")
      (fields
        (field (name "MANUFACTURER") "Kamaya")
        (field (name "MANUFACTURER PART NUMBER") "RMC1-3R30FTE")
        (field (name "TOLERANCE") "1%")
        (field (name ".CASE/PACKAGE") "2512")
        (field (name ".TOLERANCE") "1%")
        (field (name "SUPPLIER PART NUMBER 1") "791-RMC1-3R30FTE")
      )
      (libsource (lib "RESISTOR_Kamaya_RMC1-3R30FTE") (part "RMC1-3R30FTE"))
    )
    (comp (ref "R4")
      (value "10Ω")
      (footprint "SR2512JK-0710RL")
      (fields
        (field (name "MANUFACTURER") "Yageo Group")
        (field (name "MANUFACTURER PART NUMBER") "SR2512JK-0710RL")
        (field (name "TOLERANCE") "5%")
        (field (name ".CASE/PACKAGE") "2512")
        (field (name ".TOLERANCE") "5%")
        (field (name "SUPPLIER PART NUMBER 1") "603-SR2512JK-0710RL")
      )
      (libsource (lib "RESISTOR_Yageo_SR2512JK-0710RL") (part "SR2512JK-0710RL"))
    )
    (comp (ref "R5")
      (value "3.3Ω")
      (footprint "RMC1-3R30FTE")
      (fields
        (field (name "MANUFACTURER") "Kamaya")
        (field (name "MANUFACTURER PART NUMBER") "RMC1-3R30FTE")
        (field (name "TOLERANCE") "1%")
        (field (name ".CASE/PACKAGE") "2512")
        (field (name ".TOLERANCE") "1%")
        (field (name "SUPPLIER PART NUMBER 1") "791-RMC1-3R30FTE")
      )
      (libsource (lib "RESISTOR_Kamaya_RMC1-3R30FTE") (part "RMC1-3R30FTE"))
    )
    (comp (ref "R6")
      (value "10Ω")
      (footprint "SR2512JK-0710RL")
      (fields
        (field (name "MANUFACTURER") "Yageo Group")
        (field (name "MANUFACTURER PART NUMBER") "SR2512JK-0710RL")
        (field (name "TOLERANCE") "5%")
        (field (name ".CASE/PACKAGE") "2512")
        (field (name ".TOLERANCE") "5%")
        (field (name "SUPPLIER PART NUMBER 1") "603-SR2512JK-0710RL")
      )
      (libsource (lib "RESISTOR_Yageo_SR2512JK-0710RL") (part "SR2512JK-0710RL"))
    )
    (comp (ref "R7")
      (value "3.3Ω")
      (footprint "RMC1-3R30FTE")
      (fields
        (field (name "MANUFACTURER") "Kamaya")
        (field (name "MANUFACTURER PART NUMBER") "RMC1-3R30FTE")
        (field (name "TOLERANCE") "1%")
        (field (name ".CASE/PACKAGE") "2512")
        (field (name ".TOLERANCE") "1%")
        (field (name "SUPPLIER PART NUMBER 1") "791-RMC1-3R30FTE")
      )
      (libsource (lib "RESISTOR_Kamaya_RMC1-3R30FTE") (part "RMC1-3R30FTE"))
    )
    (comp (ref "R8")
      (value "10Ω")
      (footprint "SR2512JK-0710RL")
      (fields
        (field (name "MANUFACTURER") "Yageo Group")
        (field (name "MANUFACTURER PART NUMBER") "SR2512JK-0710RL")
        (field (name "TOLERANCE") "5%")
        (field (name ".CASE/PACKAGE") "2512")
        (field (name ".TOLERANCE") "5%")
        (field (name "SUPPLIER PART NUMBER 1") "603-SR2512JK-0710RL")
      )
      (libsource (lib "RESISTOR_Yageo_SR2512JK-0710RL") (part "SR2512JK-0710RL"))
    )
    (comp (ref "R9")
      (value "3.3Ω")
      (footprint "RMC1-3R30FTE")
      (fields
        (field (name "MANUFACTURER") "Kamaya")
        (field (name "MANUFACTURER PART NUMBER") "RMC1-3R30FTE")
        (field (name "TOLERANCE") "1%")
        (field (name ".CASE/PACKAGE") "2512")
        (field (name ".TOLERANCE") "1%")
        (field (name "SUPPLIER PART NUMBER 1") "791-RMC1-3R30FTE")
      )
      (libsource (lib "RESISTOR_Kamaya_RMC1-3R30FTE") (part "RMC1-3R30FTE"))
    )
    (comp (ref "R11")
      (value "3.09kΩ")
      (footprint "R0603 - YAGEO")
      (description "Res Thick Film 0603 3.09K Ohm 1% 0.1W(1/10W) ±100ppm/C Pad SMD T/R")
      (fields
        (field (name "MANUFACTURER") "Yageo Group")
        (field (name "MANUFACTURER PART NUMBER") "RC0603FR-073K09L")
        (field (name ".CASE/PACKAGE") "0603")
        (field (name ".TOLERANCE") "1%")
        (field (name "SUPPLIER PART NUMBER 1") "603-RC0603FR-073K09L")
      )
      (libsource (lib "RESISTOR_RC0603FR-073K09L") (part "RESISTOR - GENERIC"))
    )
    (comp (ref "R12")
      (value "3.09kΩ")
      (footprint "R0603 - YAGEO")
      (description "Res Thick Film 0603 3.09K Ohm 1% 0.1W(1/10W) ±100ppm/C Pad SMD T/R")
      (fields
        (field (name "MANUFACTURER") "Yageo Group")
        (field (name "MANUFACTURER PART NUMBER") "RC0603FR-073K09L")
        (field (name ".CASE/PACKAGE") "0603")
        (field (name ".TOLERANCE") "1%")
        (field (name "SUPPLIER PART NUMBER 1") "603-RC0603FR-073K09L")
      )
      (libsource (lib "RESISTOR_RC0603FR-073K09L") (part "RESISTOR - GENERIC"))
    )
    (comp (ref "R13")
      (value "10kΩ")
      (footprint "R0603 - YAGEO")
      (description "Res Thick Film 0603 10K Ohm 5% 1/10W ±100ppm/°C Molded SMD SMD Paper T/R")
      (fields
        (field (name "MANUFACTURER") "Yageo Group")
        (field (name "MANUFACTURER PART NUMBER") "RC0603JR-0710KL")
        (field (name ".CASE/PACKAGE") "0603")
        (field (name ".TOLERANCE") "5%")
        (field (name "SUPPLIER PART NUMBER 1") "603-RC0603JR-0710KL")
      )
      (libsource (lib "RESISTOR_RC0603JR-0710KL") (part "RC0603JR-0710KL"))
    )
    (comp (ref "R14")
      (value "10kΩ")
      (footprint "R0603 - YAGEO")
      (description "Res Thick Film 0603 10K Ohm 5% 1/10W ±100ppm/°C Molded SMD SMD Paper T/R")
      (fields
        (field (name "MANUFACTURER") "Yageo Group")
        (field (name "MANUFACTURER PART NUMBER") "RC0603JR-0710KL")
        (field (name ".CASE/PACKAGE") "0603")
        (field (name ".TOLERANCE") "5%")
        (field (name "SUPPLIER PART NUMBER 1") "603-RC0603JR-0710KL")
      )
      (libsource (lib "RESISTOR_RC0603JR-0710KL") (part "RC0603JR-0710KL"))
    )
    (comp (ref "R15")
      (value "100kΩ")
      (footprint "MFR200FRF73-100K")
      (description "Fixed Resistor, Metal Film, 2W, 100000ohm, 500V, 1% +/-Tol, 100ppm/Cel, Through Hole Mount")
      (fields
        (field (name "MANUFACTURER") "Yageo Group")
        (field (name "MANUFACTURER PART NUMBER") "MFR200FRF73-100K")
        (field (name ".CASE/PACKAGE") "Metal")
        (field (name ".TOLERANCE") "1%")
        (field (name "SUPPLIER PART NUMBER 1") "603-MFR200FRF73-100K")
      )
      (libsource (lib "RES_Yageo_MFR200FRF73-100K") (part "MFR200FRF73-100K"))
    )
    (comp (ref "R16")
      (value "3.09kΩ")
      (footprint "R0603 - YAGEO")
      (description "Res Thick Film 0603 3.09K Ohm 1% 0.1W(1/10W) ±100ppm/C Pad SMD T/R")
      (fields
        (field (name "MANUFACTURER") "Yageo Group")
        (field (name "MANUFACTURER PART NUMBER") "RC0603FR-073K09L")
        (field (name ".CASE/PACKAGE") "0603")
        (field (name ".TOLERANCE") "1%")
        (field (name "SUPPLIER PART NUMBER 1") "603-RC0603FR-073K09L")
      )
      (libsource (lib "RESISTOR_RC0603FR-073K09L") (part "RESISTOR - GENERIC"))
    )
    (comp (ref "R17")
      (value "3.09kΩ")
      (footprint "R0603 - YAGEO")
      (description "Res Thick Film 0603 3.09K Ohm 1% 0.1W(1/10W) ±100ppm/C Pad SMD T/R")
      (fields
        (field (name "MANUFACTURER") "Yageo Group")
        (field (name "MANUFACTURER PART NUMBER") "RC0603FR-073K09L")
        (field (name ".CASE/PACKAGE") "0603")
        (field (name ".TOLERANCE") "1%")
        (field (name "SUPPLIER PART NUMBER 1") "603-RC0603FR-073K09L")
      )
      (libsource (lib "RESISTOR_RC0603FR-073K09L") (part "RESISTOR - GENERIC"))
    )
    (comp (ref "R18")
      (value "10kΩ")
      (footprint "R0603 - YAGEO")
      (description "Res Thick Film 0603 10K Ohm 5% 1/10W ±100ppm/°C Molded SMD SMD Paper T/R")
      (fields
        (field (name "MANUFACTURER") "Yageo Group")
        (field (name "MANUFACTURER PART NUMBER") "RC0603JR-0710KL")
        (field (name ".CASE/PACKAGE") "0603")
        (field (name ".TOLERANCE") "5%")
        (field (name "SUPPLIER PART NUMBER 1") "603-RC0603JR-0710KL")
      )
      (libsource (lib "RESISTOR_RC0603JR-0710KL") (part "RC0603JR-0710KL"))
    )
    (comp (ref "R19")
      (value "10kΩ")
      (footprint "R0603 - YAGEO")
      (description "Res Thick Film 0603 10K Ohm 5% 1/10W ±100ppm/°C Molded SMD SMD Paper T/R")
      (fields
        (field (name "MANUFACTURER") "Yageo Group")
        (field (name "MANUFACTURER PART NUMBER") "RC0603JR-0710KL")
        (field (name ".CASE/PACKAGE") "0603")
        (field (name ".TOLERANCE") "5%")
        (field (name "SUPPLIER PART NUMBER 1") "603-RC0603JR-0710KL")
      )
      (libsource (lib "RESISTOR_RC0603JR-0710KL") (part "RC0603JR-0710KL"))
    )
    (comp (ref "R20")
      (value "1kΩ")
      (footprint "R0603 - YAGEO")
      (description "Fixed Resistor, Metal Glaze/Thick Film, 0.1W, 1000ohm, 75V, 1% +/-Tol, Surface Mount, 0603")
      (fields
        (field (name "MANUFACTURER") "Yageo Group")
        (field (name "MANUFACTURER PART NUMBER") "RC0603FR-071KL")
        (field (name ".CASE/PACKAGE") "0603")
        (field (name ".TOLERANCE") "1%")
        (field (name "SUPPLIER PART NUMBER 1") "603-RC0603FR-071KL")
      )
      (libsource (lib "RESISTOR_Yageo_RC0603FR-071KL") (part "RC0603FR-071KL"))
    )
    (comp (ref "R21")
      (value "1kΩ")
      (footprint "R0603 - YAGEO")
      (description "Fixed Resistor, Metal Glaze/Thick Film, 0.1W, 1000ohm, 75V, 1% +/-Tol, Surface Mount, 0603")
      (fields
        (field (name "MANUFACTURER") "Yageo Group")
        (field (name "MANUFACTURER PART NUMBER") "RC0603FR-071KL")
        (field (name ".CASE/PACKAGE") "0603")
        (field (name ".TOLERANCE") "1%")
        (field (name "SUPPLIER PART NUMBER 1") "603-RC0603FR-071KL")
      )
      (libsource (lib "RESISTOR_Yageo_RC0603FR-071KL") (part "RC0603FR-071KL"))
    )
    (comp (ref "R22")
      (value "1kΩ")
      (footprint "R0603 - YAGEO")
      (description "Fixed Resistor, Metal Glaze/Thick Film, 0.1W, 1000ohm, 75V, 1% +/-Tol, Surface Mount, 0603")
      (fields
        (field (name "MANUFACTURER") "Yageo Group")
        (field (name "MANUFACTURER PART NUMBER") "RC0603FR-071KL")
        (field (name ".CASE/PACKAGE") "0603")
        (field (name ".TOLERANCE") "1%")
        (field (name "SUPPLIER PART NUMBER 1") "603-RC0603FR-071KL")
      )
      (libsource (lib "RESISTOR_Yageo_RC0603FR-071KL") (part "RC0603FR-071KL"))
    )
    (comp (ref "R23")
      (value "1kΩ")
      (footprint "R0603 - YAGEO")
      (description "Fixed Resistor, Metal Glaze/Thick Film, 0.1W, 1000ohm, 75V, 1% +/-Tol, Surface Mount, 0603")
      (fields
        (field (name "MANUFACTURER") "Yageo Group")
        (field (name "MANUFACTURER PART NUMBER") "RC0603FR-071KL")
        (field (name ".CASE/PACKAGE") "0603")
        (field (name ".TOLERANCE") "1%")
        (field (name "SUPPLIER PART NUMBER 1") "603-RC0603FR-071KL")
      )
      (libsource (lib "RESISTOR_Yageo_RC0603FR-071KL") (part "RC0603FR-071KL"))
    )
    (comp (ref "R24")
      (value "1kΩ")
      (footprint "RC0805JR-101KL")
      (description "Res Thick Film 0805 1K Ohm 5% 0.125W(1/8W) ±100ppm/C Pad SMD T/R")
      (fields
        (field (name "MANUFACTURER") "Yageo Group")
        (field (name "MANUFACTURER PART NUMBER") "RC0805JR-101KL")
        (field (name ".CASE/PACKAGE") "0805")
        (field (name ".TOLERANCE") "5%")
        (field (name "SUPPLIER PART NUMBER 1") "603-RC0805JR-101KL")
      )
      (libsource (lib "RESISTOR_Yageo_RC0805JR-101KL") (part "RC0805JR-101KL"))
    )
    (comp (ref "R25")
      (value "10kΩ")
      (footprint "RC0805JR-101KL")
      (fields
        (field (name "MANUFACTURER") "Yageo Group")
        (field (name "MANUFACTURER PART NUMBER") "AA0805FR-0710KL")
        (field (name "TOLERANCE") "1%")
        (field (name ".CASE/PACKAGE") "0805")
        (field (name ".TOLERANCE") "1%")
        (field (name "SUPPLIER PART NUMBER 2") "603-AA0805FR-0710KL")
      )
      (libsource (lib "Sch_components") (part "AA0805FR-0710KL"))
    )
    (comp (ref "R26")
      (value "10kΩ")
      (footprint "RC0805JR-101KL")
      (fields
        (field (name "MANUFACTURER") "Yageo Group")
        (field (name "MANUFACTURER PART NUMBER") "AA0805FR-0710KL")
        (field (name "TOLERANCE") "1%")
        (field (name ".CASE/PACKAGE") "0805")
        (field (name ".TOLERANCE") "1%")
        (field (name "SUPPLIER PART NUMBER 2") "603-AA0805FR-0710KL")
      )
      (libsource (lib "Sch_components") (part "AA0805FR-0710KL"))
    )
    (comp (ref "R27")
      (value "10kΩ")
      (footprint "RC0805JR-101KL")
      (fields
        (field (name "MANUFACTURER") "Yageo Group")
        (field (name "MANUFACTURER PART NUMBER") "AA0805FR-0710KL")
        (field (name "TOLERANCE") "1%")
        (field (name ".CASE/PACKAGE") "0805")
        (field (name ".TOLERANCE") "1%")
        (field (name "SUPPLIER PART NUMBER 2") "603-AA0805FR-0710KL")
      )
      (libsource (lib "Sch_components") (part "AA0805FR-0710KL"))
    )
    (comp (ref "R28")
      (value "10kΩ")
      (footprint "RC0805JR-101KL")
      (fields
        (field (name "MANUFACTURER") "Yageo Group")
        (field (name "MANUFACTURER PART NUMBER") "AA0805FR-0710KL")
        (field (name "TOLERANCE") "1%")
        (field (name ".CASE/PACKAGE") "0805")
        (field (name ".TOLERANCE") "1%")
        (field (name "SUPPLIER PART NUMBER 2") "603-AA0805FR-0710KL")
      )
      (libsource (lib "Sch_components") (part "AA0805FR-0710KL"))
    )
    (comp (ref "S1")
      (value "SW_DPDT_CAS-220TB1")
      (footprint "CAS-220-TB1")
      (libsource (lib "SW_CAS-220TB1") (part "SW_DPDT_CAS-220TB1"))
    )
    (comp (ref "S2")
      (value "SW_DPDT_CAS-220TB1")
      (footprint "CAS-220-TB1")
      (libsource (lib "SW_CAS-220TB1") (part "SW_DPDT_CAS-220TB1"))
    )
    (comp (ref "T2")
      (value "THM_Test_Points")
      (footprint "Test_Point")
      (libsource (lib "THM_TestPoints_Keystone") (part "THM_Test_Points"))
    )
    (comp (ref "T3")
      (value "THM_Test_Points")
      (footprint "Test_Point")
      (libsource (lib "THM_TestPoints_Keystone") (part "THM_Test_Points"))
    )
    (comp (ref "T4")
      (value "THM_Test_Points")
      (footprint "Test_Point")
      (libsource (lib "THM_TestPoints_Keystone") (part "THM_Test_Points"))
    )
    (comp (ref "T5")
      (value "THM_Test_Points")
      (footprint "Test_Point")
      (libsource (lib "THM_TestPoints_Keystone") (part "THM_Test_Points"))
    )
    (comp (ref "T6")
      (value "THM_Test_Points")
      (footprint "Test_Point")
      (libsource (lib "THM_TestPoints_Keystone") (part "THM_Test_Points"))
    )
    (comp (ref "T7")
      (value "THM_Test_Points")
      (footprint "Test_Point")
      (libsource (lib "THM_TestPoints_Keystone") (part "THM_Test_Points"))
    )
    (comp (ref "T8")
      (value "THM_Test_Points")
      (footprint "Test_Point")
      (libsource (lib "THM_TestPoints_Keystone") (part "THM_Test_Points"))
    )
    (comp (ref "T9")
      (value "THM_Test_Points")
      (footprint "Test_Point")
      (libsource (lib "THM_TestPoints_Keystone") (part "THM_Test_Points"))
    )
    (comp (ref "T10")
      (value "THM_Test_Points")
      (footprint "Test_Point")
      (libsource (lib "THM_TestPoints_Keystone") (part "THM_Test_Points"))
    )
    (comp (ref "T11")
      (value "THM_Test_Points")
      (footprint "Test_Point")
      (libsource (lib "THM_TestPoints_Keystone") (part "THM_Test_Points"))
    )
    (comp (ref "T12")
      (value "THM_Test_Points")
      (footprint "Test_Point")
      (libsource (lib "THM_TestPoints_Keystone") (part "THM_Test_Points"))
    )
    (comp (ref "T13")
      (value "THM_Test_Points")
      (footprint "Test_Point")
      (libsource (lib "THM_TestPoints_Keystone") (part "THM_Test_Points"))
    )
    (comp (ref "T14")
      (value "THM_Test_Points")
      (footprint "Test_Point")
      (libsource (lib "THM_TestPoints_Keystone") (part "THM_Test_Points"))
    )
    (comp (ref "T15")
      (value "THM_Test_Points")
      (footprint "Test_Point")
      (libsource (lib "THM_TestPoints_Keystone") (part "THM_Test_Points"))
    )
    (comp (ref "T16")
      (value "THM_Test_Points")
      (footprint "Test_Point")
      (libsource (lib "THM_TestPoints_Keystone") (part "THM_Test_Points"))
    )
    (comp (ref "T17")
      (value "THM_Test_Points")
      (footprint "Test_Point")
      (libsource (lib "THM_TestPoints_Keystone") (part "THM_Test_Points"))
    )
    (comp (ref "T18")
      (value "THM_Test_Points")
      (footprint "Test_Point")
      (libsource (lib "THM_TestPoints_Keystone") (part "THM_Test_Points"))
    )
    (comp (ref "T19")
      (value "THM_Test_Points")
      (footprint "Test_Point")
      (libsource (lib "THM_TestPoints_Keystone") (part "THM_Test_Points"))
    )
    (comp (ref "T20")
      (value "THM_Test_Points")
      (footprint "Test_Point")
      (libsource (lib "THM_TestPoints_Keystone") (part "THM_Test_Points"))
    )
    (comp (ref "T21")
      (value "THM_Test_Points")
      (footprint "Test_Point")
      (libsource (lib "THM_TestPoints_Keystone") (part "THM_Test_Points"))
    )
    (comp (ref "T22")
      (value "THM_Test_Points")
      (footprint "Test_Point")
      (libsource (lib "THM_TestPoints_Keystone") (part "THM_Test_Points"))
    )
    (comp (ref "T23")
      (value "THM_Test_Points")
      (footprint "Test_Point")
      (libsource (lib "THM_TestPoints_Keystone") (part "THM_Test_Points"))
    )
    (comp (ref "T24")
      (value "THM_Test_Points")
      (footprint "Test_Point")
      (libsource (lib "THM_TestPoints_Keystone") (part "THM_Test_Points"))
    )
    (comp (ref "T25")
      (value "THM_Test_Points")
      (footprint "Test_Point")
      (libsource (lib "THM_TestPoints_Keystone") (part "THM_Test_Points"))
    )
    (comp (ref "T26")
      (value "THM_Test_Points")
      (footprint "Test_Point")
      (libsource (lib "THM_TestPoints_Keystone") (part "THM_Test_Points"))
    )
    (comp (ref "T27")
      (value "THM_Test_Points")
      (footprint "Test_Point")
      (libsource (lib "THM_TestPoints_Keystone") (part "THM_Test_Points"))
    )
    (comp (ref "T28")
      (value "THM_Test_Points")
      (footprint "Test_Point")
      (libsource (lib "THM_TestPoints_Keystone") (part "THM_Test_Points"))
    )
    (comp (ref "T29")
      (value "THM_Test_Points")
      (footprint "Test_Point")
      (libsource (lib "THM_TestPoints_Keystone") (part "THM_Test_Points"))
    )
    (comp (ref "U1")
      (value "NCV51152BADR2G")
      (footprint "SOIC-NCV51152BADR2G")
      (libsource (lib "Sch_components") (part "NCV51152BADR2G"))
    )
    (comp (ref "U2")
      (value "NCV51152BADR2G")
      (footprint "SOIC-NCV51152BADR2G")
      (libsource (lib "Sch_components") (part "NCV51152BADR2G"))
    )
    (comp (ref "U3")
      (value "NCV51152BADR2G")
      (footprint "SOIC-NCV51152BADR2G")
      (libsource (lib "Sch_components") (part "NCV51152BADR2G"))
    )
    (comp (ref "U4")
      (value "NCV51152BADR2G")
      (footprint "SOIC-NCV51152BADR2G")
      (libsource (lib "Sch_components") (part "NCV51152BADR2G"))
    )
    (comp (ref "U6")
      (value "74VHCT04AFT")
      (footprint "74VHCT04AFT")
      (libsource (lib "NOT_74VHC04AFT") (part "74VHCT04AFT"))
    )
    (comp (ref "U7")
      (value "74HC08T14-13")
      (footprint "74HC08T14-13")
      (libsource (lib "AND_74HC08T14-13") (part "74HC08T14-13"))
    )
    (comp (ref "U8")
      (value "SK15GH063")
      (footprint "Semikron_FB_SK15GH063:SK15GH063")
      (libsource (lib "FB_Semikron_SK15GH063") (part "SK15GH063"))
    )
    (comp (ref "U9")
      (value "74VHCT04AFT")
      (footprint "74VHCT04AFT")
      (libsource (lib "NOT_74VHC04AFT") (part "74VHCT04AFT"))
    )
    (comp (ref "U10")
      (value "74HC08T14-13")
      (footprint "74HC08T14-13")
      (libsource (lib "AND_74HC08T14-13") (part "74HC08T14-13"))
    )
  )
  (nets
    (net (code "1") (name "-Vdc") (class "Default")
      (node (ref "C13") (pin "1") (pinfunction "1_1") (pintype "passive"))
      (node (ref "C14") (pin "1") (pinfunction "1_1") (pintype "passive"))
      (node (ref "C15") (pin "1") (pinfunction "1_1") (pintype "passive"))
      (node (ref "C16") (pin "1") (pinfunction "1_1") (pintype "passive"))
      (node (ref "C26") (pin "1") (pinfunction "1_1") (pintype "passive"))
      (node (ref "C27") (pin "1") (pinfunction "1_1") (pintype "passive"))
      (node (ref "C28") (pin "1") (pinfunction "1_1") (pintype "passive"))
      (node (ref "C29") (pin "1") (pinfunction "1_1") (pintype "passive"))
      (node (ref "C30") (pin "V-") (pinfunction "2_V-") (pintype "passive"))
      (node (ref "C41") (pin "1") (pinfunction "1_1") (pintype "passive"))
      (node (ref "DCDC2") (pin "4") (pinfunction "-VOUT_4") (pintype "power_in"))
      (node (ref "DCDC4") (pin "4") (pinfunction "-VOUT_4") (pintype "power_in"))
      (node (ref "J5") (pin "1") (pinfunction "1.1_1") (pintype "passive"))
      (node (ref "J5") (pin "2") (pinfunction "1.2_2") (pintype "passive"))
      (node (ref "J5") (pin "3") (pinfunction "2.1_3") (pintype "power_in"))
      (node (ref "J5") (pin "4") (pinfunction "2.2_4") (pintype "power_in"))
      (node (ref "R15") (pin "1") (pinfunction "1_1") (pintype "passive"))
      (node (ref "R26") (pin "2") (pinfunction "2_2") (pintype "passive"))
      (node (ref "R28") (pin "2") (pinfunction "2_2") (pintype "passive"))
      (node (ref "T27") (pin "1") (pinfunction "TP_1") (pintype "passive"))
      (node (ref "T29") (pin "1") (pinfunction "TP_1") (pintype "passive"))
      (node (ref "U2") (pin "8") (pinfunction "VEE_8") (pintype "passive"))
      (node (ref "U4") (pin "8") (pinfunction "VEE_8") (pintype "passive"))
      (node (ref "U8") (pin "13") (pinfunction "-VDC_13") (pintype "power_in"))
    )
    (net (code "2") (name "/A") (class "Default")
      (node (ref "C6") (pin "1") (pinfunction "1_1") (pintype "passive"))
      (node (ref "C7") (pin "1") (pinfunction "1_1") (pintype "passive"))
      (node (ref "C8") (pin "1") (pinfunction "1_1") (pintype "passive"))
      (node (ref "C9") (pin "1") (pinfunction "1_1") (pintype "passive"))
      (node (ref "DCDC1") (pin "4") (pinfunction "-VOUT_4") (pintype "power_in"))
      (node (ref "J3") (pin "1") (pinfunction "1.1_1") (pintype "passive"))
      (node (ref "J3") (pin "2") (pinfunction "1.2_2") (pintype "passive"))
      (node (ref "J3") (pin "3") (pinfunction "2.1_3") (pintype "power_in"))
      (node (ref "J3") (pin "4") (pinfunction "2.2_4") (pintype "power_in"))
      (node (ref "R25") (pin "2") (pinfunction "2_2") (pintype "passive"))
      (node (ref "T26") (pin "1") (pinfunction "TP_1") (pintype "passive"))
      (node (ref "U1") (pin "8") (pinfunction "VEE_8") (pintype "passive"))
      (node (ref "U8") (pin "2") (pinfunction "A_2") (pintype "passive"))
    )
    (net (code "3") (name "/B") (class "Default")
      (node (ref "C19") (pin "1") (pinfunction "1_1") (pintype "passive"))
      (node (ref "C20") (pin "1") (pinfunction "1_1") (pintype "passive"))
      (node (ref "C21") (pin "1") (pinfunction "1_1") (pintype "passive"))
      (node (ref "C22") (pin "1") (pinfunction "1_1") (pintype "passive"))
      (node (ref "DCDC3") (pin "4") (pinfunction "-VOUT_4") (pintype "power_in"))
      (node (ref "J4") (pin "1") (pinfunction "1.1_1") (pintype "passive"))
      (node (ref "J4") (pin "2") (pinfunction "1.2_2") (pintype "passive"))
      (node (ref "J4") (pin "3") (pinfunction "2.1_3") (pintype "power_in"))
      (node (ref "J4") (pin "4") (pinfunction "2.2_4") (pintype "power_in"))
      (node (ref "R27") (pin "2") (pinfunction "2_2") (pintype "passive"))
      (node (ref "T28") (pin "1") (pinfunction "TP_1") (pintype "passive"))
      (node (ref "U3") (pin "8") (pinfunction "VEE_8") (pintype "passive"))
      (node (ref "U8") (pin "7") (pinfunction "B_7") (pintype "passive"))
    )
    (net (code "4") (name "/Enable_a") (class "Default")
      (node (ref "J7") (pin "1") (pinfunction "Vo_1") (pintype "passive"))
      (node (ref "R14") (pin "2") (pinfunction "2_2") (pintype "passive"))
      (node (ref "R21") (pin "1") (pinfunction "1_1") (pintype "passive"))
      (node (ref "T10") (pin "1") (pinfunction "TP_1") (pintype "passive"))
      (node (ref "U6") (pin "5") (pinfunction "3A_5") (pintype "passive"))
      (node (ref "U7") (pin "2") (pinfunction "1B_2") (pintype "passive"))
      (node (ref "U7") (pin "5") (pinfunction "2B_5") (pintype "passive"))
      (node (ref "U7") (pin "9") (pinfunction "3B_9") (pintype "passive"))
    )
    (net (code "5") (name "/Enable_b") (class "Default")
      (node (ref "J9") (pin "1") (pinfunction "Vo_1") (pintype "passive"))
      (node (ref "R19") (pin "2") (pinfunction "2_2") (pintype "passive"))
      (node (ref "R23") (pin "1") (pinfunction "1_1") (pintype "passive"))
      (node (ref "T20") (pin "1") (pinfunction "TP_1") (pintype "passive"))
      (node (ref "U10") (pin "12") (pinfunction "4B_12") (pintype "passive"))
      (node (ref "U10") (pin "2") (pinfunction "1B_2") (pintype "passive"))
      (node (ref "U10") (pin "5") (pinfunction "2B_5") (pintype "passive"))
      (node (ref "U9") (pin "5") (pinfunction "3A_5") (pintype "passive"))
    )
    (net (code "6") (name "/G1") (class "Default")
      (node (ref "R2") (pin "2") (pinfunction "2_2") (pintype "passive"))
      (node (ref "R25") (pin "1") (pinfunction "1_1") (pintype "passive"))
      (node (ref "R3") (pin "2") (pinfunction "2_2") (pintype "passive"))
      (node (ref "T7") (pin "1") (pinfunction "TP_1") (pintype "passive"))
      (node (ref "U8") (pin "1") (pinfunction "G1_1") (pintype "input"))
    )
    (net (code "7") (name "/G2") (class "Default")
      (node (ref "R26") (pin "1") (pinfunction "1_1") (pintype "passive"))
      (node (ref "R4") (pin "2") (pinfunction "2_2") (pintype "passive"))
      (node (ref "R5") (pin "2") (pinfunction "2_2") (pintype "passive"))
      (node (ref "T11") (pin "1") (pinfunction "TP_1") (pintype "passive"))
      (node (ref "U8") (pin "9") (pinfunction "G2_9") (pintype "input"))
    )
    (net (code "8") (name "/G3") (class "Default")
      (node (ref "R27") (pin "1") (pinfunction "1_1") (pintype "passive"))
      (node (ref "R6") (pin "2") (pinfunction "2_2") (pintype "passive"))
      (node (ref "R7") (pin "2") (pinfunction "2_2") (pintype "passive"))
      (node (ref "T14") (pin "1") (pinfunction "TP_1") (pintype "passive"))
      (node (ref "U8") (pin "8") (pinfunction "G3_8") (pintype "input"))
    )
    (net (code "9") (name "/G4") (class "Default")
      (node (ref "R28") (pin "1") (pinfunction "1_1") (pintype "passive"))
      (node (ref "R8") (pin "2") (pinfunction "2_2") (pintype "passive"))
      (node (ref "R9") (pin "2") (pinfunction "2_2") (pintype "passive"))
      (node (ref "T21") (pin "1") (pinfunction "TP_1") (pintype "passive"))
      (node (ref "U8") (pin "16") (pinfunction "G4_16") (pintype "input"))
    )
    (net (code "10") (name "/S1") (class "Default")
      (node (ref "S1") (pin "5") (pinfunction "(C)_5_5") (pintype "passive"))
      (node (ref "T6") (pin "1") (pinfunction "TP_1") (pintype "passive"))
      (node (ref "U1") (pin "2") (pinfunction "IN+_2") (pintype "input"))
    )
    (net (code "11") (name "/S2") (class "Default")
      (node (ref "S1") (pin "2") (pinfunction "2_(C)_2") (pintype "passive"))
      (node (ref "T5") (pin "1") (pinfunction "TP_1") (pintype "passive"))
      (node (ref "U2") (pin "2") (pinfunction "IN+_2") (pintype "input"))
    )
    (net (code "12") (name "/S3") (class "Default")
      (node (ref "S2") (pin "2") (pinfunction "2_(C)_2") (pintype "passive"))
      (node (ref "T16") (pin "1") (pinfunction "TP_1") (pintype "passive"))
      (node (ref "U3") (pin "2") (pinfunction "IN+_2") (pintype "input"))
    )
    (net (code "13") (name "/S4") (class "Default")
      (node (ref "S2") (pin "5") (pinfunction "(C)_5_5") (pintype "passive"))
      (node (ref "T17") (pin "1") (pinfunction "TP_1") (pintype "passive"))
      (node (ref "U4") (pin "2") (pinfunction "IN+_2") (pintype "input"))
    )
    (net (code "14") (name "/Sa") (class "Default")
      (node (ref "J6") (pin "1") (pinfunction "Vo_1") (pintype "passive"))
      (node (ref "R13") (pin "2") (pinfunction "2_2") (pintype "passive"))
      (node (ref "R20") (pin "1") (pinfunction "1_1") (pintype "passive"))
      (node (ref "T4") (pin "1") (pinfunction "TP_1") (pintype "passive"))
      (node (ref "U6") (pin "1") (pinfunction "1A_1") (pintype "passive"))
      (node (ref "U7") (pin "13") (pinfunction "4A_13") (pintype "passive"))
    )
    (net (code "15") (name "/Sa*") (class "Default")
      (node (ref "S1") (pin "4") (pinfunction "4_4") (pintype "passive"))
      (node (ref "T3") (pin "1") (pinfunction "TP_1") (pintype "passive"))
      (node (ref "U7") (pin "3") (pinfunction "1Y_3") (pintype "passive"))
    )
    (net (code "16") (name "/Sa_dt") (class "Default")
      (node (ref "C32") (pin "2") (pinfunction "2_2") (pintype "passive"))
      (node (ref "D1") (pin "2") (pinfunction "2_2") (pintype "passive"))
      (node (ref "R11") (pin "1") (pinfunction "1_1") (pintype "passive"))
      (node (ref "U7") (pin "1") (pinfunction "1A_1") (pintype "passive"))
    )
    (net (code "17") (name "/San*") (class "Default")
      (node (ref "S1") (pin "3") (pinfunction "3_3") (pintype "passive"))
      (node (ref "T8") (pin "1") (pinfunction "TP_1") (pintype "passive"))
      (node (ref "U7") (pin "8") (pinfunction "3Y_8") (pintype "passive"))
    )
    (net (code "18") (name "/Sap*") (class "Default")
      (node (ref "S1") (pin "6") (pinfunction "6_6") (pintype "passive"))
      (node (ref "T9") (pin "1") (pinfunction "TP_1") (pintype "passive"))
      (node (ref "U7") (pin "11") (pinfunction "4Y_11") (pintype "passive"))
    )
    (net (code "19") (name "/Sb") (class "Default")
      (node (ref "J8") (pin "1") (pinfunction "Vo_1") (pintype "passive"))
      (node (ref "R18") (pin "2") (pinfunction "2_2") (pintype "passive"))
      (node (ref "R22") (pin "1") (pinfunction "1_1") (pintype "passive"))
      (node (ref "T15") (pin "1") (pinfunction "TP_1") (pintype "passive"))
      (node (ref "U10") (pin "10") (pinfunction "3A_10") (pintype "passive"))
      (node (ref "U9") (pin "1") (pinfunction "1A_1") (pintype "passive"))
    )
    (net (code "20") (name "/Sb*") (class "Default")
      (node (ref "S2") (pin "1") (pinfunction "1_1") (pintype "passive"))
      (node (ref "T13") (pin "1") (pinfunction "TP_1") (pintype "passive"))
      (node (ref "U10") (pin "6") (pinfunction "2Y_6") (pintype "passive"))
    )
    (net (code "21") (name "/Sb_dt") (class "Default")
      (node (ref "C34") (pin "2") (pinfunction "2_2") (pintype "passive"))
      (node (ref "D3") (pin "2") (pinfunction "2_2") (pintype "passive"))
      (node (ref "R16") (pin "1") (pinfunction "1_1") (pintype "passive"))
      (node (ref "U10") (pin "4") (pinfunction "2A_4") (pintype "passive"))
    )
    (net (code "22") (name "/Sbn*") (class "Default")
      (node (ref "S2") (pin "6") (pinfunction "6_6") (pintype "passive"))
      (node (ref "T19") (pin "1") (pinfunction "TP_1") (pintype "passive"))
      (node (ref "U10") (pin "11") (pinfunction "4Y_11") (pintype "passive"))
    )
    (net (code "23") (name "/Sbp*") (class "Default")
      (node (ref "S2") (pin "3") (pinfunction "3_3") (pintype "passive"))
      (node (ref "T18") (pin "1") (pinfunction "TP_1") (pintype "passive"))
      (node (ref "U10") (pin "8") (pinfunction "3Y_8") (pintype "passive"))
    )
    (net (code "24") (name "/VCC1") (class "Default")
      (node (ref "C6") (pin "2") (pinfunction "2_2") (pintype "passive"))
      (node (ref "C7") (pin "2") (pinfunction "2_2") (pintype "passive"))
      (node (ref "C8") (pin "2") (pinfunction "2_2") (pintype "passive"))
      (node (ref "C9") (pin "2") (pinfunction "2_2") (pintype "passive"))
      (node (ref "DCDC1") (pin "5") (pinfunction "+VOUT_5") (pintype "power_in"))
      (node (ref "U1") (pin "5") (pinfunction "VCC_5") (pintype "power_in"))
    )
    (net (code "25") (name "/VCC2") (class "Default")
      (node (ref "C13") (pin "2") (pinfunction "2_2") (pintype "passive"))
      (node (ref "C14") (pin "2") (pinfunction "2_2") (pintype "passive"))
      (node (ref "C15") (pin "2") (pinfunction "2_2") (pintype "passive"))
      (node (ref "C16") (pin "2") (pinfunction "2_2") (pintype "passive"))
      (node (ref "DCDC2") (pin "5") (pinfunction "+VOUT_5") (pintype "power_in"))
      (node (ref "U2") (pin "5") (pinfunction "VCC_5") (pintype "power_in"))
    )
    (net (code "26") (name "/VCC3") (class "Default")
      (node (ref "C19") (pin "2") (pinfunction "2_2") (pintype "passive"))
      (node (ref "C20") (pin "2") (pinfunction "2_2") (pintype "passive"))
      (node (ref "C21") (pin "2") (pinfunction "2_2") (pintype "passive"))
      (node (ref "C22") (pin "2") (pinfunction "2_2") (pintype "passive"))
      (node (ref "DCDC3") (pin "5") (pinfunction "+VOUT_5") (pintype "power_in"))
      (node (ref "U3") (pin "5") (pinfunction "VCC_5") (pintype "power_in"))
    )
    (net (code "27") (name "/VCC4") (class "Default")
      (node (ref "C26") (pin "2") (pinfunction "2_2") (pintype "passive"))
      (node (ref "C27") (pin "2") (pinfunction "2_2") (pintype "passive"))
      (node (ref "C28") (pin "2") (pinfunction "2_2") (pintype "passive"))
      (node (ref "C29") (pin "2") (pinfunction "2_2") (pintype "passive"))
      (node (ref "DCDC4") (pin "5") (pinfunction "+VOUT_5") (pintype "power_in"))
      (node (ref "U4") (pin "5") (pinfunction "VCC_5") (pintype "power_in"))
    )
    (net (code "28") (name "/nEnable_a") (class "Default")
      (node (ref "U6") (pin "6") (pinfunction "3Y_6") (pintype "passive"))
      (node (ref "U7") (pin "12") (pinfunction "4B_12") (pintype "passive"))
    )
    (net (code "29") (name "/nEnable_b") (class "Default")
      (node (ref "U10") (pin "9") (pinfunction "3B_9") (pintype "passive"))
      (node (ref "U9") (pin "6") (pinfunction "3Y_6") (pintype "passive"))
    )
    (net (code "30") (name "/nSa") (class "Default")
      (node (ref "D2") (pin "1") (pinfunction "1_1") (pintype "passive"))
      (node (ref "R12") (pin "2") (pinfunction "2_2") (pintype "passive"))
      (node (ref "U6") (pin "13") (pinfunction "6A_13") (pintype "passive"))
      (node (ref "U6") (pin "2") (pinfunction "1Y_2") (pintype "passive"))
      (node (ref "U7") (pin "10") (pinfunction "3A_10") (pintype "passive"))
    )
    (net (code "31") (name "/nSa*") (class "Default")
      (node (ref "S1") (pin "1") (pinfunction "1_1") (pintype "passive"))
      (node (ref "T2") (pin "1") (pinfunction "TP_1") (pintype "passive"))
      (node (ref "U7") (pin "6") (pinfunction "2Y_6") (pintype "passive"))
    )
    (net (code "32") (name "/nSa_dt") (class "Default")
      (node (ref "C33") (pin "2") (pinfunction "2_2") (pintype "passive"))
      (node (ref "D2") (pin "2") (pinfunction "2_2") (pintype "passive"))
      (node (ref "R12") (pin "1") (pinfunction "1_1") (pintype "passive"))
      (node (ref "U7") (pin "4") (pinfunction "2A_4") (pintype "passive"))
    )
    (net (code "33") (name "/nSb") (class "Default")
      (node (ref "D4") (pin "1") (pinfunction "1_1") (pintype "passive"))
      (node (ref "R17") (pin "2") (pinfunction "2_2") (pintype "passive"))
      (node (ref "U10") (pin "13") (pinfunction "4A_13") (pintype "passive"))
      (node (ref "U9") (pin "13") (pinfunction "6A_13") (pintype "passive"))
      (node (ref "U9") (pin "2") (pinfunction "1Y_2") (pintype "passive"))
    )
    (net (code "34") (name "/nSb*") (class "Default")
      (node (ref "S2") (pin "4") (pinfunction "4_4") (pintype "passive"))
      (node (ref "T12") (pin "1") (pinfunction "TP_1") (pintype "passive"))
      (node (ref "U10") (pin "3") (pinfunction "1Y_3") (pintype "passive"))
    )
    (net (code "35") (name "/nSb_dt") (class "Default")
      (node (ref "C35") (pin "2") (pinfunction "2_2") (pintype "passive"))
      (node (ref "D4") (pin "2") (pinfunction "2_2") (pintype "passive"))
      (node (ref "R17") (pin "1") (pinfunction "1_1") (pintype "passive"))
      (node (ref "U10") (pin "1") (pinfunction "1A_1") (pintype "passive"))
    )
    (net (code "36") (name "5V") (class "Default")
      (node (ref "C1") (pin "1") (pinfunction "1_1") (pintype "passive"))
      (node (ref "C10") (pin "1") (pinfunction "1_1") (pintype "passive"))
      (node (ref "C11") (pin "2") (pinfunction "2_2") (pintype "passive"))
      (node (ref "C17") (pin "2") (pinfunction "2_2") (pintype "passive"))
      (node (ref "C2") (pin "1") (pinfunction "1_1") (pintype "passive"))
      (node (ref "C23") (pin "1") (pinfunction "1_1") (pintype "passive"))
      (node (ref "C24") (pin "2") (pinfunction "2_2") (pintype "passive"))
      (node (ref "C3") (pin "2") (pinfunction "2_2") (pintype "passive"))
      (node (ref "C37") (pin "1") (pinfunction "1_1") (pintype "passive"))
      (node (ref "C38") (pin "1") (pinfunction "1_1") (pintype "passive"))
      (node (ref "C39") (pin "1") (pinfunction "1_1") (pintype "passive"))
      (node (ref "C4") (pin "2") (pinfunction "2_2") (pintype "passive"))
      (node (ref "C40") (pin "1") (pinfunction "1_1") (pintype "passive"))
      (node (ref "C42") (pin "2") (pinfunction "2_2") (pintype "passive"))
      (node (ref "C43") (pin "2") (pinfunction "2_2") (pintype "passive"))
      (node (ref "C44") (pin "2") (pinfunction "2_2") (pintype "passive"))
      (node (ref "C45") (pin "2") (pinfunction "2_2") (pintype "passive"))
      (node (ref "C46") (pin "2") (pinfunction "2_2") (pintype "passive"))
      (node (ref "C47") (pin "2") (pinfunction "2_2") (pintype "passive"))
      (node (ref "C48") (pin "2") (pinfunction "2_2") (pintype "passive"))
      (node (ref "C49") (pin "2") (pinfunction "2_2") (pintype "passive"))
      (node (ref "D5") (pin "2") (pinfunction "2_2") (pintype "passive"))
      (node (ref "J1") (pin "2") (pinfunction "1.2_2") (pintype "passive"))
      (node (ref "J1") (pin "4") (pinfunction "2.2_4") (pintype "power_in"))
      (node (ref "J6") (pin "3") (pinfunction "VCC_3") (pintype "passive"))
      (node (ref "J7") (pin "3") (pinfunction "VCC_3") (pintype "passive"))
      (node (ref "J8") (pin "3") (pinfunction "VCC_3") (pintype "passive"))
      (node (ref "J9") (pin "3") (pinfunction "VCC_3") (pintype "passive"))
      (node (ref "L1") (pin "1") (pinfunction "1_1") (pintype "passive"))
      (node (ref "L2") (pin "1") (pinfunction "1_1") (pintype "passive"))
      (node (ref "L3") (pin "1") (pinfunction "1_1") (pintype "passive"))
      (node (ref "L4") (pin "1") (pinfunction "1_1") (pintype "passive"))
      (node (ref "R20") (pin "2") (pinfunction "2_2") (pintype "passive"))
      (node (ref "R21") (pin "2") (pinfunction "2_2") (pintype "passive"))
      (node (ref "R22") (pin "2") (pinfunction "2_2") (pintype "passive"))
      (node (ref "R23") (pin "2") (pinfunction "2_2") (pintype "passive"))
      (node (ref "U1") (pin "1") (pinfunction "VDD_1") (pintype "power_in"))
      (node (ref "U10") (pin "14") (pinfunction "VDD_14") (pintype "passive"))
      (node (ref "U2") (pin "1") (pinfunction "VDD_1") (pintype "power_in"))
      (node (ref "U3") (pin "1") (pinfunction "VDD_1") (pintype "power_in"))
      (node (ref "U4") (pin "1") (pinfunction "VDD_1") (pintype "power_in"))
      (node (ref "U6") (pin "14") (pinfunction "VDD_14") (pintype "passive"))
      (node (ref "U7") (pin "14") (pinfunction "VDD_14") (pintype "passive"))
      (node (ref "U9") (pin "14") (pinfunction "VDD_14") (pintype "passive"))
    )
    (net (code "37") (name "GND") (class "Default")
      (node (ref "C1") (pin "2") (pinfunction "2_2") (pintype "passive"))
      (node (ref "C10") (pin "2") (pinfunction "2_2") (pintype "passive"))
      (node (ref "C11") (pin "1") (pinfunction "1_1") (pintype "passive"))
      (node (ref "C12") (pin "1") (pinfunction "1_1") (pintype "passive"))
      (node (ref "C17") (pin "1") (pinfunction "1_1") (pintype "passive"))
      (node (ref "C18") (pin "1") (pinfunction "1_1") (pintype "passive"))
      (node (ref "C2") (pin "2") (pinfunction "2_2") (pintype "passive"))
      (node (ref "C23") (pin "2") (pinfunction "2_2") (pintype "passive"))
      (node (ref "C24") (pin "1") (pinfunction "1_1") (pintype "passive"))
      (node (ref "C25") (pin "1") (pinfunction "1_1") (pintype "passive"))
      (node (ref "C3") (pin "1") (pinfunction "1_1") (pintype "passive"))
      (node (ref "C32") (pin "1") (pinfunction "1_1") (pintype "passive"))
      (node (ref "C33") (pin "1") (pinfunction "1_1") (pintype "passive"))
      (node (ref "C34") (pin "1") (pinfunction "1_1") (pintype "passive"))
      (node (ref "C35") (pin "1") (pinfunction "1_1") (pintype "passive"))
      (node (ref "C37") (pin "2") (pinfunction "2_2") (pintype "passive"))
      (node (ref "C38") (pin "2") (pinfunction "2_2") (pintype "passive"))
      (node (ref "C39") (pin "2") (pinfunction "2_2") (pintype "passive"))
      (node (ref "C4") (pin "1") (pinfunction "1_1") (pintype "passive"))
      (node (ref "C40") (pin "2") (pinfunction "2_2") (pintype "passive"))
      (node (ref "C42") (pin "1") (pinfunction "1_1") (pintype "passive"))
      (node (ref "C43") (pin "1") (pinfunction "1_1") (pintype "passive"))
      (node (ref "C44") (pin "1") (pinfunction "1_1") (pintype "passive"))
      (node (ref "C45") (pin "1") (pinfunction "1_1") (pintype "passive"))
      (node (ref "C46") (pin "1") (pinfunction "1_1") (pintype "passive"))
      (node (ref "C47") (pin "1") (pinfunction "1_1") (pintype "passive"))
      (node (ref "C48") (pin "1") (pinfunction "1_1") (pintype "passive"))
      (node (ref "C49") (pin "1") (pinfunction "1_1") (pintype "passive"))
      (node (ref "C5") (pin "1") (pinfunction "1_1") (pintype "passive"))
      (node (ref "DCDC1") (pin "1") (pinfunction "-VIN_1") (pintype "power_in"))
      (node (ref "DCDC2") (pin "1") (pinfunction "-VIN_1") (pintype "power_in"))
      (node (ref "DCDC3") (pin "1") (pinfunction "-VIN_1") (pintype "power_in"))
      (node (ref "DCDC4") (pin "1") (pinfunction "-VIN_1") (pintype "power_in"))
      (node (ref "J1") (pin "1") (pinfunction "1.1_1") (pintype "passive"))
      (node (ref "J1") (pin "3") (pinfunction "2.1_3") (pintype "power_in"))
      (node (ref "J6") (pin "2") (pinfunction "GND_2") (pintype "passive"))
      (node (ref "J7") (pin "2") (pinfunction "GND_2") (pintype "passive"))
      (node (ref "J8") (pin "2") (pinfunction "GND_2") (pintype "passive"))
      (node (ref "J9") (pin "2") (pinfunction "GND_2") (pintype "passive"))
      (node (ref "R13") (pin "1") (pinfunction "1_1") (pintype "passive"))
      (node (ref "R14") (pin "1") (pinfunction "1_1") (pintype "passive"))
      (node (ref "R18") (pin "1") (pinfunction "1_1") (pintype "passive"))
      (node (ref "R19") (pin "1") (pinfunction "1_1") (pintype "passive"))
      (node (ref "R24") (pin "1") (pinfunction "1_1") (pintype "passive"))
      (node (ref "T22") (pin "1") (pinfunction "TP_1") (pintype "passive"))
      (node (ref "T23") (pin "1") (pinfunction "TP_1") (pintype "passive"))
      (node (ref "T24") (pin "1") (pinfunction "TP_1") (pintype "passive"))
      (node (ref "T25") (pin "1") (pinfunction "TP_1") (pintype "passive"))
      (node (ref "U1") (pin "3") (pinfunction "IN-_3") (pintype "input"))
      (node (ref "U1") (pin "4") (pinfunction "GND_4") (pintype "passive"))
      (node (ref "U10") (pin "7") (pinfunction "GND_7") (pintype "passive"))
      (node (ref "U2") (pin "3") (pinfunction "IN-_3") (pintype "input"))
      (node (ref "U2") (pin "4") (pinfunction "GND_4") (pintype "passive"))
      (node (ref "U3") (pin "3") (pinfunction "IN-_3") (pintype "input"))
      (node (ref "U3") (pin "4") (pinfunction "GND_4") (pintype "passive"))
      (node (ref "U4") (pin "3") (pinfunction "IN-_3") (pintype "input"))
      (node (ref "U4") (pin "4") (pinfunction "GND_4") (pintype "passive"))
      (node (ref "U6") (pin "7") (pinfunction "GND_7") (pintype "passive"))
      (node (ref "U7") (pin "7") (pinfunction "GND_7") (pintype "passive"))
      (node (ref "U9") (pin "7") (pinfunction "GND_7") (pintype "passive"))
    )
    (net (code "38") (name "Net-(D5-Pad1)") (class "Default")
      (node (ref "D5") (pin "1") (pinfunction "1_1") (pintype "passive"))
      (node (ref "R24") (pin "2") (pinfunction "2_2") (pintype "passive"))
    )
    (net (code "39") (name "Net-(DCDC1-+VIN)") (class "Default")
      (node (ref "C5") (pin "2") (pinfunction "2_2") (pintype "passive"))
      (node (ref "DCDC1") (pin "2") (pinfunction "+VIN_2") (pintype "power_in"))
      (node (ref "L1") (pin "2") (pinfunction "2_2") (pintype "passive"))
    )
    (net (code "40") (name "Net-(DCDC2-+VIN)") (class "Default")
      (node (ref "C12") (pin "2") (pinfunction "2_2") (pintype "passive"))
      (node (ref "DCDC2") (pin "2") (pinfunction "+VIN_2") (pintype "power_in"))
      (node (ref "L2") (pin "2") (pinfunction "2_2") (pintype "passive"))
    )
    (net (code "41") (name "Net-(DCDC3-+VIN)") (class "Default")
      (node (ref "C18") (pin "2") (pinfunction "2_2") (pintype "passive"))
      (node (ref "DCDC3") (pin "2") (pinfunction "+VIN_2") (pintype "power_in"))
      (node (ref "L3") (pin "2") (pinfunction "2_2") (pintype "passive"))
    )
    (net (code "42") (name "Net-(DCDC4-+VIN)") (class "Default")
      (node (ref "C25") (pin "2") (pinfunction "2_2") (pintype "passive"))
      (node (ref "DCDC4") (pin "2") (pinfunction "+VIN_2") (pintype "power_in"))
      (node (ref "L4") (pin "2") (pinfunction "2_2") (pintype "passive"))
    )
    (net (code "43") (name "Net-(U1-OUTH)") (class "Default")
      (node (ref "R3") (pin "1") (pinfunction "1_1") (pintype "passive"))
      (node (ref "U1") (pin "6") (pinfunction "OUTH_6") (pintype "output"))
    )
    (net (code "44") (name "Net-(U1-OUTL)") (class "Default")
      (node (ref "R2") (pin "1") (pinfunction "1_1") (pintype "passive"))
      (node (ref "U1") (pin "7") (pinfunction "OUTL_7") (pintype "output"))
    )
    (net (code "45") (name "Net-(U2-OUTH)") (class "Default")
      (node (ref "R5") (pin "1") (pinfunction "1_1") (pintype "passive"))
      (node (ref "U2") (pin "6") (pinfunction "OUTH_6") (pintype "output"))
    )
    (net (code "46") (name "Net-(U2-OUTL)") (class "Default")
      (node (ref "R4") (pin "1") (pinfunction "1_1") (pintype "passive"))
      (node (ref "U2") (pin "7") (pinfunction "OUTL_7") (pintype "output"))
    )
    (net (code "47") (name "Net-(U3-OUTH)") (class "Default")
      (node (ref "R7") (pin "1") (pinfunction "1_1") (pintype "passive"))
      (node (ref "U3") (pin "6") (pinfunction "OUTH_6") (pintype "output"))
    )
    (net (code "48") (name "Net-(U3-OUTL)") (class "Default")
      (node (ref "R6") (pin "1") (pinfunction "1_1") (pintype "passive"))
      (node (ref "U3") (pin "7") (pinfunction "OUTL_7") (pintype "output"))
    )
    (net (code "49") (name "Net-(U4-OUTH)") (class "Default")
      (node (ref "R9") (pin "1") (pinfunction "1_1") (pintype "passive"))
      (node (ref "U4") (pin "6") (pinfunction "OUTH_6") (pintype "output"))
    )
    (net (code "50") (name "Net-(U4-OUTL)") (class "Default")
      (node (ref "R8") (pin "1") (pinfunction "1_1") (pintype "passive"))
      (node (ref "U4") (pin "7") (pinfunction "OUTL_7") (pintype "output"))
    )
    (net (code "51") (name "Net-(U6-6Y)") (class "Default")
      (node (ref "D1") (pin "1") (pinfunction "1_1") (pintype "passive"))
      (node (ref "R11") (pin "2") (pinfunction "2_2") (pintype "passive"))
      (node (ref "U6") (pin "12") (pinfunction "6Y_12") (pintype "passive"))
    )
    (net (code "52") (name "Net-(U9-6Y)") (class "Default")
      (node (ref "D3") (pin "1") (pinfunction "1_1") (pintype "passive"))
      (node (ref "R16") (pin "2") (pinfunction "2_2") (pintype "passive"))
      (node (ref "U9") (pin "12") (pinfunction "6Y_12") (pintype "passive"))
    )
    (net (code "53") (name "Vdc") (class "Default")
      (node (ref "C30") (pin "V+") (pinfunction "1_V+") (pintype "passive"))
      (node (ref "C41") (pin "2") (pinfunction "2_2") (pintype "passive"))
      (node (ref "J2") (pin "1") (pinfunction "1.1_1") (pintype "passive"))
      (node (ref "J2") (pin "2") (pinfunction "1.2_2") (pintype "passive"))
      (node (ref "J2") (pin "3") (pinfunction "2.1_3") (pintype "power_in"))
      (node (ref "J2") (pin "4") (pinfunction "2.2_4") (pintype "power_in"))
      (node (ref "R15") (pin "2") (pinfunction "2_2") (pintype "passive"))
      (node (ref "U8") (pin "5") (pinfunction "VDC_5") (pintype "power_in"))
    )
    (net (code "54") (name "unconnected-(DCDC1-NC-Pad8)") (class "Default")
      (node (ref "DCDC1") (pin "8") (pinfunction "NC_8") (pintype "passive"))
    )
    (net (code "55") (name "unconnected-(DCDC2-NC-Pad8)") (class "Default")
      (node (ref "DCDC2") (pin "8") (pinfunction "NC_8") (pintype "passive"))
    )
    (net (code "56") (name "unconnected-(DCDC3-NC-Pad8)") (class "Default")
      (node (ref "DCDC3") (pin "8") (pinfunction "NC_8") (pintype "passive"))
    )
    (net (code "57") (name "unconnected-(DCDC4-NC-Pad8)") (class "Default")
      (node (ref "DCDC4") (pin "8") (pinfunction "NC_8") (pintype "passive"))
    )
    (net (code "58") (name "unconnected-(J6-NC-Pad5)") (class "Default")
      (node (ref "J6") (pin "5") (pinfunction "NC_5") (pintype "passive"))
    )
    (net (code "59") (name "unconnected-(J6-NC-Pad8)") (class "Default")
      (node (ref "J6") (pin "8") (pinfunction "NC_8") (pintype "passive"))
    )
    (net (code "60") (name "unconnected-(J6-RL-Pad4)") (class "Default")
      (node (ref "J6") (pin "4") (pinfunction "RL_4") (pintype "passive"))
    )
    (net (code "61") (name "unconnected-(J7-NC-Pad5)") (class "Default")
      (node (ref "J7") (pin "5") (pinfunction "NC_5") (pintype "passive"))
    )
    (net (code "62") (name "unconnected-(J7-NC-Pad8)") (class "Default")
      (node (ref "J7") (pin "8") (pinfunction "NC_8") (pintype "passive"))
    )
    (net (code "63") (name "unconnected-(J7-RL-Pad4)") (class "Default")
      (node (ref "J7") (pin "4") (pinfunction "RL_4") (pintype "passive"))
    )
    (net (code "64") (name "unconnected-(J8-NC-Pad5)") (class "Default")
      (node (ref "J8") (pin "5") (pinfunction "NC_5") (pintype "passive"))
    )
    (net (code "65") (name "unconnected-(J8-NC-Pad8)") (class "Default")
      (node (ref "J8") (pin "8") (pinfunction "NC_8") (pintype "passive"))
    )
    (net (code "66") (name "unconnected-(J8-RL-Pad4)") (class "Default")
      (node (ref "J8") (pin "4") (pinfunction "RL_4") (pintype "passive"))
    )
    (net (code "67") (name "unconnected-(J9-NC-Pad5)") (class "Default")
      (node (ref "J9") (pin "5") (pinfunction "NC_5") (pintype "passive"))
    )
    (net (code "68") (name "unconnected-(J9-NC-Pad8)") (class "Default")
      (node (ref "J9") (pin "8") (pinfunction "NC_8") (pintype "passive"))
    )
    (net (code "69") (name "unconnected-(J9-RL-Pad4)") (class "Default")
      (node (ref "J9") (pin "4") (pinfunction "RL_4") (pintype "passive"))
    )
    (net (code "70") (name "unconnected-(U6-2A-Pad3)") (class "Default")
      (node (ref "U6") (pin "3") (pinfunction "2A_3") (pintype "passive"))
    )
    (net (code "71") (name "unconnected-(U6-2Y-Pad4)") (class "Default")
      (node (ref "U6") (pin "4") (pinfunction "2Y_4") (pintype "passive"))
    )
    (net (code "72") (name "unconnected-(U6-4A-Pad9)") (class "Default")
      (node (ref "U6") (pin "9") (pinfunction "4A_9") (pintype "passive"))
    )
    (net (code "73") (name "unconnected-(U6-4Y-Pad8)") (class "Default")
      (node (ref "U6") (pin "8") (pinfunction "4Y_8") (pintype "passive"))
    )
    (net (code "74") (name "unconnected-(U6-5A-Pad11)") (class "Default")
      (node (ref "U6") (pin "11") (pinfunction "5A_11") (pintype "passive"))
    )
    (net (code "75") (name "unconnected-(U6-5Y-Pad10)") (class "Default")
      (node (ref "U6") (pin "10") (pinfunction "5Y_10") (pintype "passive"))
    )
    (net (code "76") (name "unconnected-(U9-2A-Pad3)") (class "Default")
      (node (ref "U9") (pin "3") (pinfunction "2A_3") (pintype "passive"))
    )
    (net (code "77") (name "unconnected-(U9-2Y-Pad4)") (class "Default")
      (node (ref "U9") (pin "4") (pinfunction "2Y_4") (pintype "passive"))
    )
    (net (code "78") (name "unconnected-(U9-4A-Pad9)") (class "Default")
      (node (ref "U9") (pin "9") (pinfunction "4A_9") (pintype "passive"))
    )
    (net (code "79") (name "unconnected-(U9-4Y-Pad8)") (class "Default")
      (node (ref "U9") (pin "8") (pinfunction "4Y_8") (pintype "passive"))
    )
    (net (code "80") (name "unconnected-(U9-5A-Pad11)") (class "Default")
      (node (ref "U9") (pin "11") (pinfunction "5A_11") (pintype "passive"))
    )
    (net (code "81") (name "unconnected-(U9-5Y-Pad10)") (class "Default")
      (node (ref "U9") (pin "10") (pinfunction "5Y_10") (pintype "passive"))
    )
  )
)
